# NOMIDI_Controller_005_fix.net
KiCad netlist of a schematic drawn in EAGLE
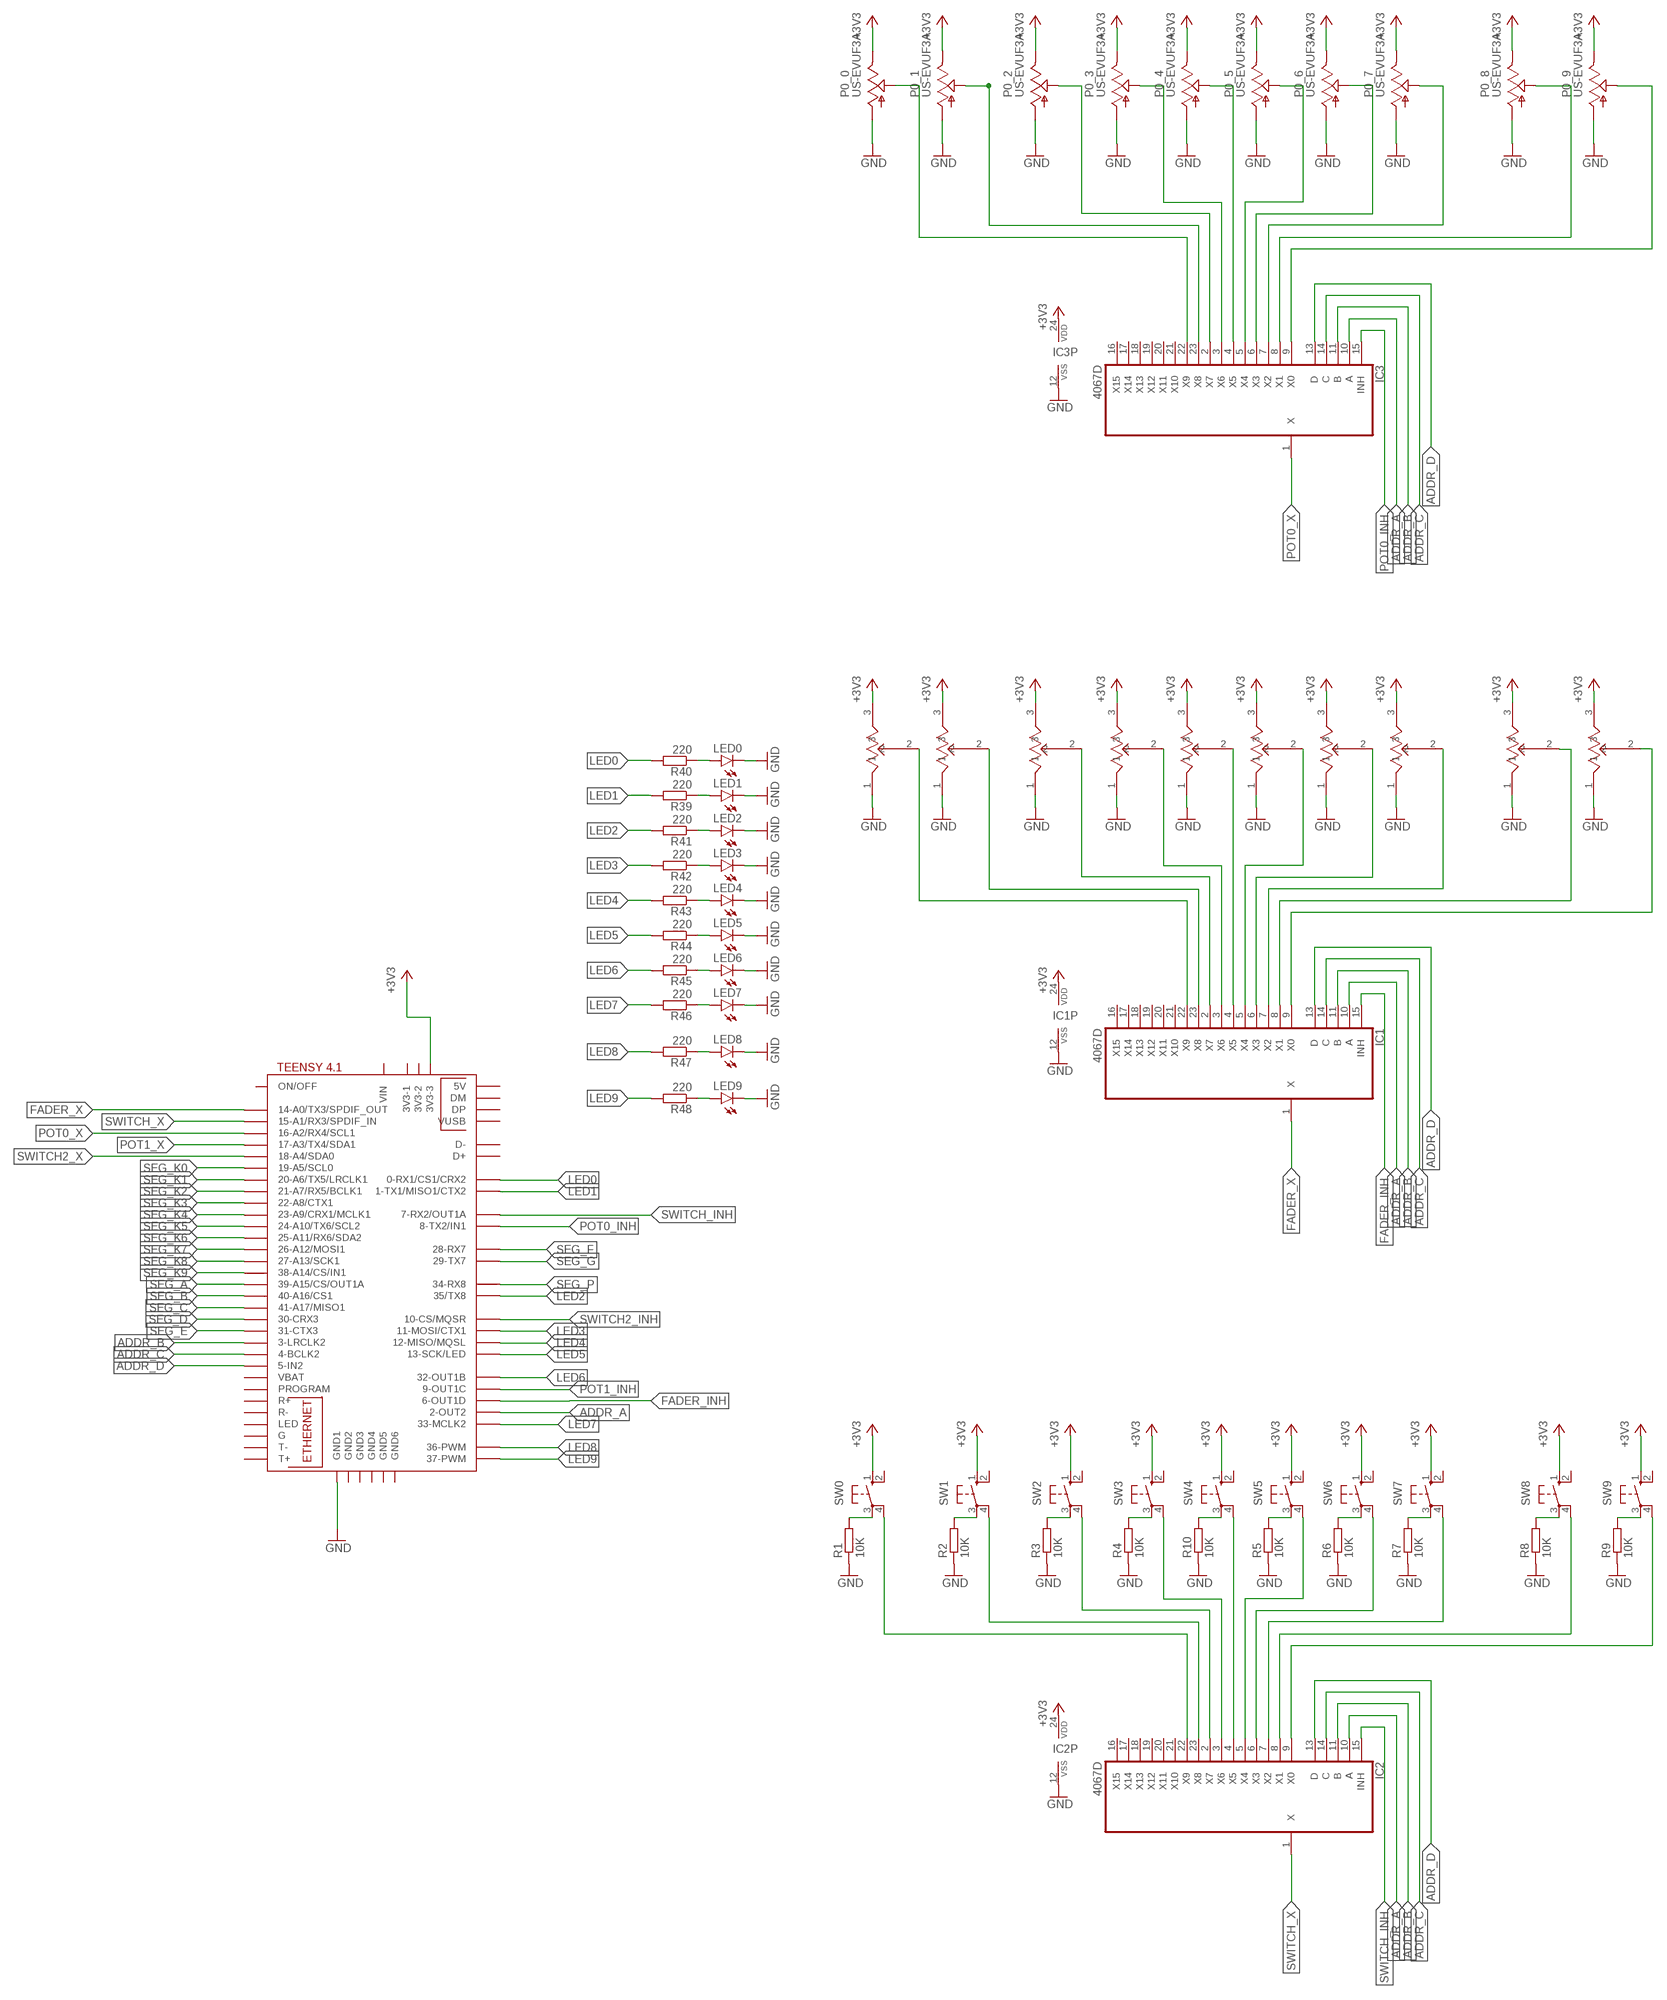
[diagram p0: schematic, sheet 1, part 1 of 3]
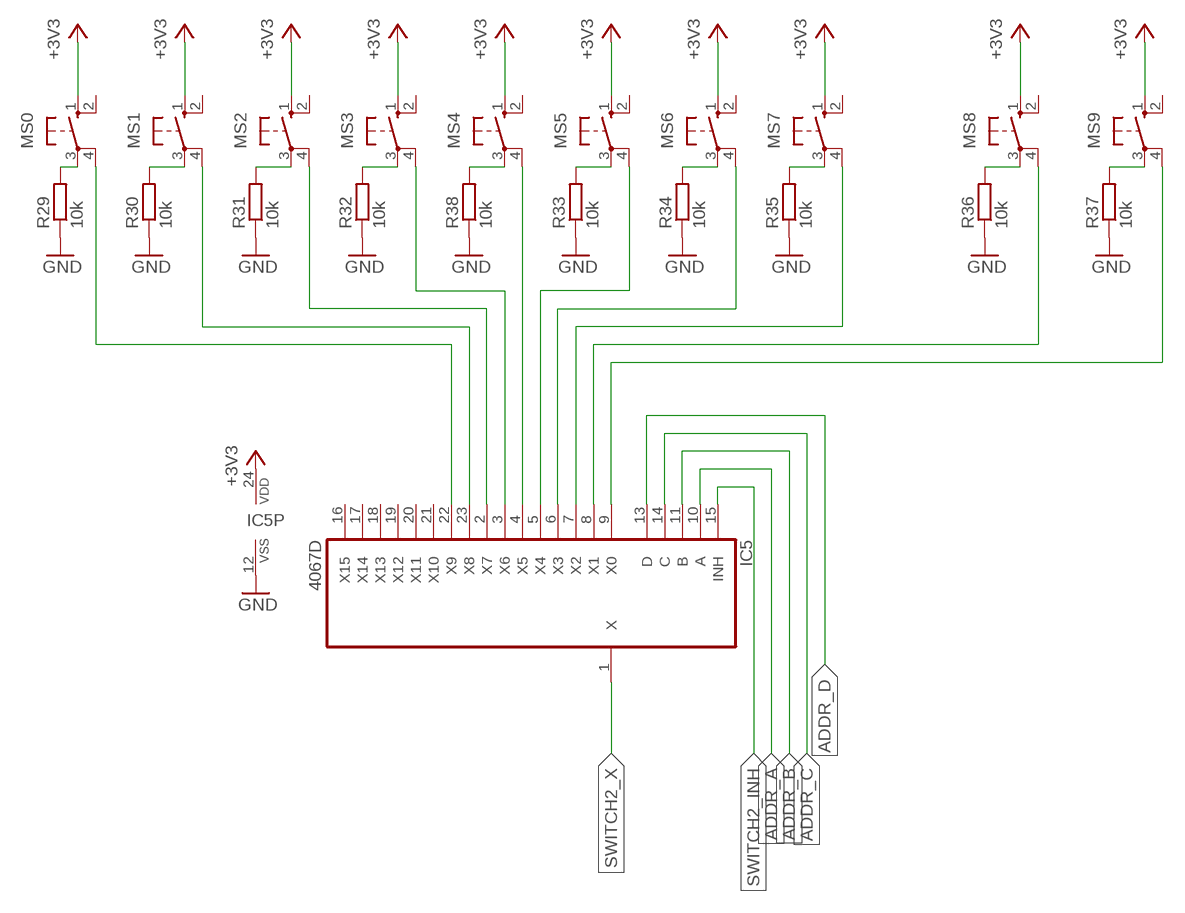
[diagram p1: schematic, sheet 1, part 2 of 3]
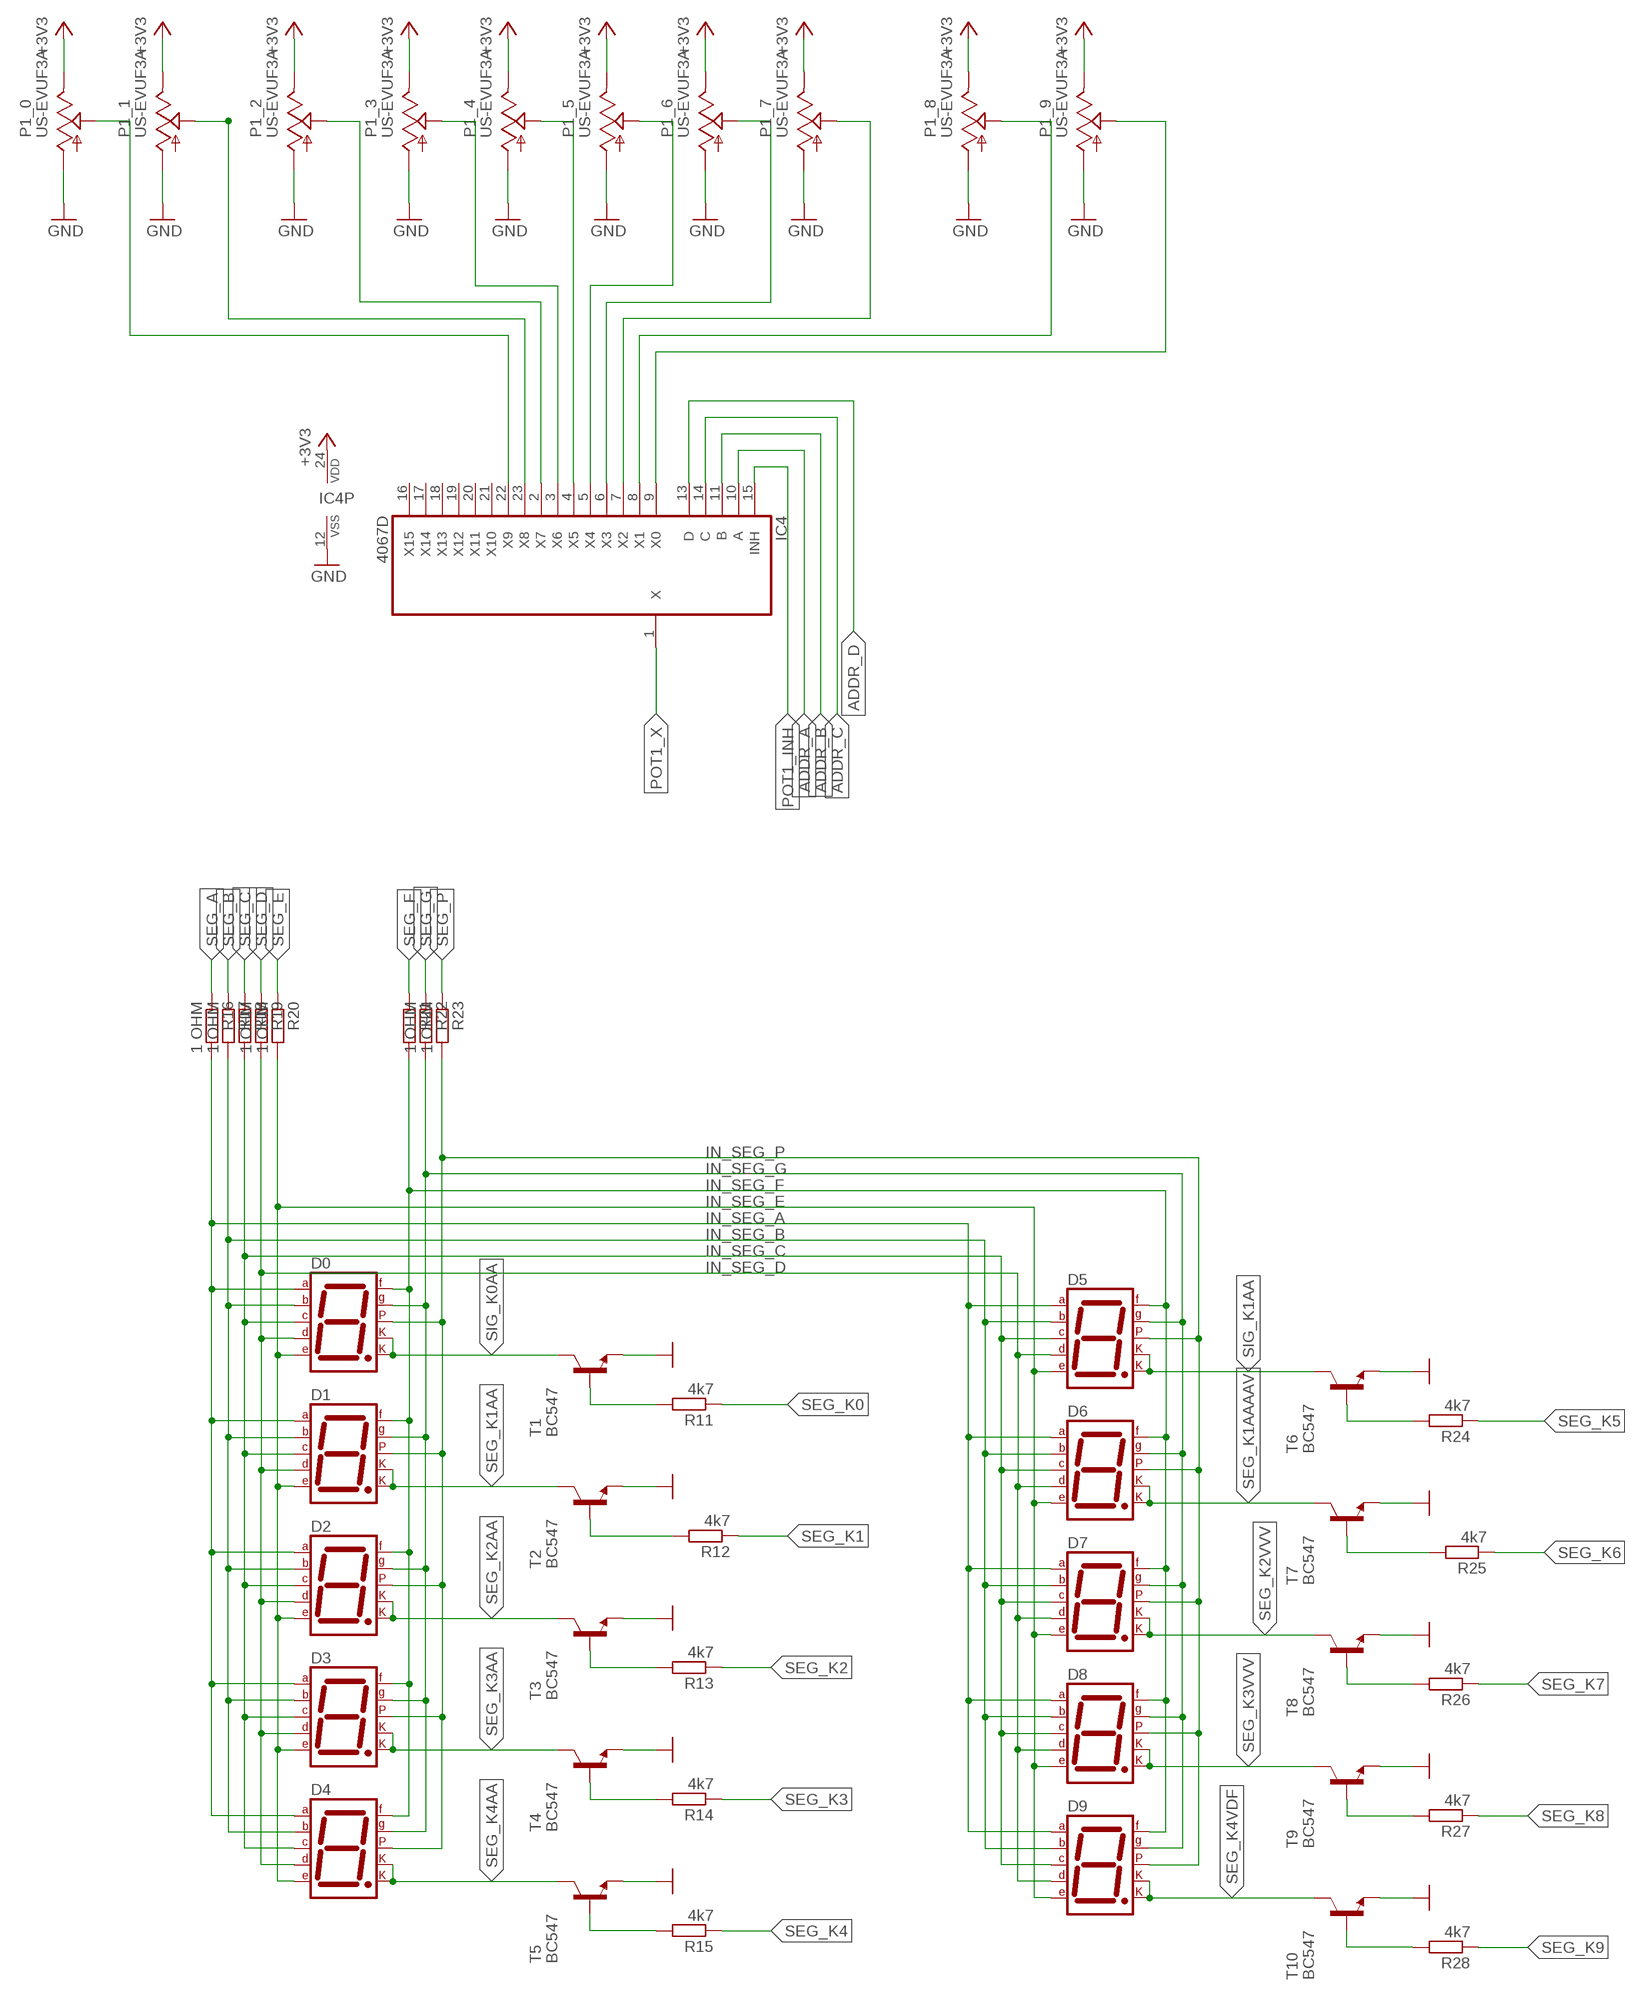
[diagram p2: schematic, sheet 1, part 3 of 3]

(export (version "E")
  (design (tool "Eeschema 10.0.6"))
  (components
    (comp (ref "D0")
      (value "7SEG-CK")
      (footprint "eagle-import:7SEG-13")
      (libsource (lib "eagle-import") (part "7SEG-CK"))
    )
    (comp (ref "D1")
      (value "7SEG-CK")
      (footprint "eagle-import:7SEG-13")
      (libsource (lib "eagle-import") (part "7SEG-CK"))
    )
    (comp (ref "D2")
      (value "7SEG-CK")
      (footprint "eagle-import:7SEG-13")
      (libsource (lib "eagle-import") (part "7SEG-CK"))
    )
    (comp (ref "D3")
      (value "7SEG-CK")
      (footprint "eagle-import:7SEG-13")
      (libsource (lib "eagle-import") (part "7SEG-CK"))
    )
    (comp (ref "D4")
      (value "7SEG-CK")
      (footprint "eagle-import:7SEG-13")
      (libsource (lib "eagle-import") (part "7SEG-CK"))
    )
    (comp (ref "D5")
      (value "7SEG-CK")
      (footprint "eagle-import:7SEG-13")
      (libsource (lib "eagle-import") (part "7SEG-CK"))
    )
    (comp (ref "D6")
      (value "7SEG-CK")
      (footprint "eagle-import:7SEG-13")
      (libsource (lib "eagle-import") (part "7SEG-CK"))
    )
    (comp (ref "D7")
      (value "7SEG-CK")
      (footprint "eagle-import:7SEG-13")
      (libsource (lib "eagle-import") (part "7SEG-CK"))
    )
    (comp (ref "D8")
      (value "7SEG-CK")
      (footprint "eagle-import:7SEG-13")
      (libsource (lib "eagle-import") (part "7SEG-CK"))
    )
    (comp (ref "D9")
      (value "7SEG-CK")
      (footprint "eagle-import:7SEG-13")
      (libsource (lib "eagle-import") (part "7SEG-CK"))
    )
    (comp (ref "IC1")
      (value "4067D")
      (footprint "eagle-import:SO24W")
      (libsource (lib "eagle-import") (part "4067D"))
    )
    (comp (ref "IC2")
      (value "4067D")
      (footprint "eagle-import:SO24W")
      (libsource (lib "eagle-import") (part "4067D"))
    )
    (comp (ref "IC3")
      (value "4067D")
      (footprint "eagle-import:SO24W")
      (libsource (lib "eagle-import") (part "4067D"))
    )
    (comp (ref "IC4")
      (value "4067D")
      (footprint "eagle-import:SO24W")
      (libsource (lib "eagle-import") (part "4067D"))
    )
    (comp (ref "IC5")
      (value "4067D")
      (footprint "eagle-import:SO24W")
      (libsource (lib "eagle-import") (part "4067D"))
    )
    (comp (ref "LED0")
      (value "LED3MM")
      (footprint "eagle-import:LED3MM")
      (libsource (lib "eagle-import") (part "LED3MM"))
    )
    (comp (ref "LED1")
      (value "LED3MM")
      (footprint "eagle-import:LED3MM")
      (libsource (lib "eagle-import") (part "LED3MM"))
    )
    (comp (ref "LED2")
      (value "LED3MM")
      (footprint "eagle-import:LED3MM")
      (libsource (lib "eagle-import") (part "LED3MM"))
    )
    (comp (ref "LED3")
      (value "LED3MM")
      (footprint "eagle-import:LED3MM")
      (libsource (lib "eagle-import") (part "LED3MM"))
    )
    (comp (ref "LED4")
      (value "LED3MM")
      (footprint "eagle-import:LED3MM")
      (libsource (lib "eagle-import") (part "LED3MM"))
    )
    (comp (ref "LED5")
      (value "LED3MM")
      (footprint "eagle-import:LED3MM")
      (libsource (lib "eagle-import") (part "LED3MM"))
    )
    (comp (ref "LED6")
      (value "LED3MM")
      (footprint "eagle-import:LED3MM")
      (libsource (lib "eagle-import") (part "LED3MM"))
    )
    (comp (ref "LED7")
      (value "LED3MM")
      (footprint "eagle-import:LED3MM")
      (libsource (lib "eagle-import") (part "LED3MM"))
    )
    (comp (ref "LED8")
      (value "LED3MM")
      (footprint "eagle-import:LED3MM")
      (libsource (lib "eagle-import") (part "LED3MM"))
    )
    (comp (ref "LED9")
      (value "LED3MM")
      (footprint "eagle-import:LED3MM")
      (libsource (lib "eagle-import") (part "LED3MM"))
    )
    (comp (ref "M0")
      (value "SLIDEPOT-ALPS-60MM")
      (footprint "eagle-import:RS6011SP600")
      (libsource (lib "eagle-import") (part "SLIDEPOT-ALPS-60MM"))
    )
    (comp (ref "M1")
      (value "SLIDEPOT-ALPS-60MM")
      (footprint "eagle-import:RS6011SP600")
      (libsource (lib "eagle-import") (part "SLIDEPOT-ALPS-60MM"))
    )
    (comp (ref "MS0")
      (value "10-XX")
      (footprint "eagle-import:B3F-10XX")
      (fields (field (name "MPN") "B3F-1000"))
      (libsource (lib "eagle-import") (part "10-XX"))
    )
    (comp (ref "MS1")
      (value "10-XX")
      (footprint "eagle-import:B3F-10XX")
      (fields (field (name "MPN") "B3F-1000"))
      (libsource (lib "eagle-import") (part "10-XX"))
    )
    (comp (ref "MS2")
      (value "10-XX")
      (footprint "eagle-import:B3F-10XX")
      (fields (field (name "MPN") "B3F-1000"))
      (libsource (lib "eagle-import") (part "10-XX"))
    )
    (comp (ref "MS3")
      (value "10-XX")
      (footprint "eagle-import:B3F-10XX")
      (fields (field (name "MPN") "B3F-1000"))
      (libsource (lib "eagle-import") (part "10-XX"))
    )
    (comp (ref "MS4")
      (value "10-XX")
      (footprint "eagle-import:B3F-10XX")
      (fields (field (name "MPN") "B3F-1000"))
      (libsource (lib "eagle-import") (part "10-XX"))
    )
    (comp (ref "MS5")
      (value "10-XX")
      (footprint "eagle-import:B3F-10XX")
      (fields (field (name "MPN") "B3F-1000"))
      (libsource (lib "eagle-import") (part "10-XX"))
    )
    (comp (ref "MS6")
      (value "10-XX")
      (footprint "eagle-import:B3F-10XX")
      (fields (field (name "MPN") "B3F-1000"))
      (libsource (lib "eagle-import") (part "10-XX"))
    )
    (comp (ref "MS7")
      (value "10-XX")
      (footprint "eagle-import:B3F-10XX")
      (fields (field (name "MPN") "B3F-1000"))
      (libsource (lib "eagle-import") (part "10-XX"))
    )
    (comp (ref "MS8")
      (value "10-XX")
      (footprint "eagle-import:B3F-10XX")
      (fields (field (name "MPN") "B3F-1000"))
      (libsource (lib "eagle-import") (part "10-XX"))
    )
    (comp (ref "MS9")
      (value "10-XX")
      (footprint "eagle-import:B3F-10XX")
      (fields (field (name "MPN") "B3F-1000"))
      (libsource (lib "eagle-import") (part "10-XX"))
    )
    (comp (ref "P0_0")
      (value "US-EVUF3A")
      (footprint "eagle-import:EVUF")
      (libsource (lib "eagle-import") (part "US-EVUAF3"))
    )
    (comp (ref "P0_1")
      (value "US-EVUF3A")
      (footprint "eagle-import:EVUF")
      (libsource (lib "eagle-import") (part "US-EVUAF3"))
    )
    (comp (ref "P0_2")
      (value "US-EVUF3A")
      (footprint "eagle-import:EVUF")
      (libsource (lib "eagle-import") (part "US-EVUAF3"))
    )
    (comp (ref "P0_3")
      (value "US-EVUF3A")
      (footprint "eagle-import:EVUF")
      (libsource (lib "eagle-import") (part "US-EVUAF3"))
    )
    (comp (ref "P0_4")
      (value "US-EVUF3A")
      (footprint "eagle-import:EVUF")
      (libsource (lib "eagle-import") (part "US-EVUAF3"))
    )
    (comp (ref "P0_5")
      (value "US-EVUF3A")
      (footprint "eagle-import:EVUF")
      (libsource (lib "eagle-import") (part "US-EVUAF3"))
    )
    (comp (ref "P0_6")
      (value "US-EVUF3A")
      (footprint "eagle-import:EVUF")
      (libsource (lib "eagle-import") (part "US-EVUAF3"))
    )
    (comp (ref "P0_7")
      (value "US-EVUF3A")
      (footprint "eagle-import:EVUF")
      (libsource (lib "eagle-import") (part "US-EVUAF3"))
    )
    (comp (ref "P0_8")
      (value "US-EVUF3A")
      (footprint "eagle-import:EVUF")
      (libsource (lib "eagle-import") (part "US-EVUAF3"))
    )
    (comp (ref "P0_9")
      (value "US-EVUF3A")
      (footprint "eagle-import:EVUF")
      (libsource (lib "eagle-import") (part "US-EVUAF3"))
    )
    (comp (ref "P1_0")
      (value "US-EVUF3A")
      (footprint "eagle-import:EVUF")
      (libsource (lib "eagle-import") (part "US-EVUAF3"))
    )
    (comp (ref "P1_1")
      (value "US-EVUF3A")
      (footprint "eagle-import:EVUF")
      (libsource (lib "eagle-import") (part "US-EVUAF3"))
    )
    (comp (ref "P1_2")
      (value "US-EVUF3A")
      (footprint "eagle-import:EVUF")
      (libsource (lib "eagle-import") (part "US-EVUAF3"))
    )
    (comp (ref "P1_3")
      (value "US-EVUF3A")
      (footprint "eagle-import:EVUF")
      (libsource (lib "eagle-import") (part "US-EVUAF3"))
    )
    (comp (ref "P1_4")
      (value "US-EVUF3A")
      (footprint "eagle-import:EVUF")
      (libsource (lib "eagle-import") (part "US-EVUAF3"))
    )
    (comp (ref "P1_5")
      (value "US-EVUF3A")
      (footprint "eagle-import:EVUF")
      (libsource (lib "eagle-import") (part "US-EVUAF3"))
    )
    (comp (ref "P1_6")
      (value "US-EVUF3A")
      (footprint "eagle-import:EVUF")
      (libsource (lib "eagle-import") (part "US-EVUAF3"))
    )
    (comp (ref "P1_7")
      (value "US-EVUF3A")
      (footprint "eagle-import:EVUF")
      (libsource (lib "eagle-import") (part "US-EVUAF3"))
    )
    (comp (ref "P1_8")
      (value "US-EVUF3A")
      (footprint "eagle-import:EVUF")
      (libsource (lib "eagle-import") (part "US-EVUAF3"))
    )
    (comp (ref "P1_9")
      (value "US-EVUF3A")
      (footprint "eagle-import:EVUF")
      (libsource (lib "eagle-import") (part "US-EVUAF3"))
    )
    (comp (ref "R1")
      (value "10K")
      (footprint "eagle-import:0207_7")
      (libsource (lib "eagle-import") (part "R-EU_0207/7"))
    )
    (comp (ref "R2")
      (value "10K")
      (footprint "eagle-import:0207_7")
      (libsource (lib "eagle-import") (part "R-EU_0207/7"))
    )
    (comp (ref "R3")
      (value "10K")
      (footprint "eagle-import:0207_7")
      (libsource (lib "eagle-import") (part "R-EU_0207/7"))
    )
    (comp (ref "R4")
      (value "10K")
      (footprint "eagle-import:0207_7")
      (libsource (lib "eagle-import") (part "R-EU_0207/7"))
    )
    (comp (ref "R5")
      (value "10K")
      (footprint "eagle-import:0207_7")
      (libsource (lib "eagle-import") (part "R-EU_0207/7"))
    )
    (comp (ref "R6")
      (value "10K")
      (footprint "eagle-import:0207_7")
      (libsource (lib "eagle-import") (part "R-EU_0207/7"))
    )
    (comp (ref "R7")
      (value "10K")
      (footprint "eagle-import:0207_7")
      (libsource (lib "eagle-import") (part "R-EU_0207/7"))
    )
    (comp (ref "R8")
      (value "10K")
      (footprint "eagle-import:0207_7")
      (libsource (lib "eagle-import") (part "R-EU_0207/7"))
    )
    (comp (ref "R9")
      (value "10K")
      (footprint "eagle-import:0207_7")
      (libsource (lib "eagle-import") (part "R-EU_0207/7"))
    )
    (comp (ref "R10")
      (value "10K")
      (footprint "eagle-import:0207_7")
      (libsource (lib "eagle-import") (part "R-EU_0207/7"))
    )
    (comp (ref "R11")
      (value "4k7")
      (footprint "eagle-import:0207_7")
      (libsource (lib "eagle-import") (part "R-EU_0207/7"))
    )
    (comp (ref "R12")
      (value "4k7")
      (footprint "eagle-import:0207_7")
      (libsource (lib "eagle-import") (part "R-EU_0207/7"))
    )
    (comp (ref "R13")
      (value "4k7")
      (footprint "eagle-import:0207_7")
      (libsource (lib "eagle-import") (part "R-EU_0207/7"))
    )
    (comp (ref "R14")
      (value "4k7")
      (footprint "eagle-import:0207_7")
      (libsource (lib "eagle-import") (part "R-EU_0207/7"))
    )
    (comp (ref "R15")
      (value "4k7")
      (footprint "eagle-import:0207_7")
      (libsource (lib "eagle-import") (part "R-EU_0207/7"))
    )
    (comp (ref "R16")
      (value "1 OHM")
      (footprint "eagle-import:0207_7")
      (libsource (lib "eagle-import") (part "R-EU_0207/7"))
    )
    (comp (ref "R17")
      (value "1 OHM")
      (footprint "eagle-import:0207_7")
      (libsource (lib "eagle-import") (part "R-EU_0207/7"))
    )
    (comp (ref "R18")
      (value "R-EU_0207/7")
      (footprint "eagle-import:0207_7")
      (libsource (lib "eagle-import") (part "R-EU_0207/7"))
    )
    (comp (ref "R19")
      (value "1 OHM")
      (footprint "eagle-import:0207_7")
      (libsource (lib "eagle-import") (part "R-EU_0207/7"))
    )
    (comp (ref "R20")
      (value "1 OHM")
      (footprint "eagle-import:0207_7")
      (libsource (lib "eagle-import") (part "R-EU_0207/7"))
    )
    (comp (ref "R21")
      (value "R-EU_0207/7")
      (footprint "eagle-import:0207_7")
      (libsource (lib "eagle-import") (part "R-EU_0207/7"))
    )
    (comp (ref "R22")
      (value "1 OHM")
      (footprint "eagle-import:0207_7")
      (libsource (lib "eagle-import") (part "R-EU_0207/7"))
    )
    (comp (ref "R23")
      (value "1 OHM")
      (footprint "eagle-import:0207_7")
      (libsource (lib "eagle-import") (part "R-EU_0207/7"))
    )
    (comp (ref "R24")
      (value "4k7")
      (footprint "eagle-import:0207_7")
      (libsource (lib "eagle-import") (part "R-EU_0207/7"))
    )
    (comp (ref "R25")
      (value "4k7")
      (footprint "eagle-import:0207_7")
      (libsource (lib "eagle-import") (part "R-EU_0207/7"))
    )
    (comp (ref "R26")
      (value "4k7")
      (footprint "eagle-import:0207_7")
      (libsource (lib "eagle-import") (part "R-EU_0207/7"))
    )
    (comp (ref "R27")
      (value "4k7")
      (footprint "eagle-import:0207_7")
      (libsource (lib "eagle-import") (part "R-EU_0207/7"))
    )
    (comp (ref "R28")
      (value "4k7")
      (footprint "eagle-import:0207_7")
      (libsource (lib "eagle-import") (part "R-EU_0207/7"))
    )
    (comp (ref "R29")
      (value "10k")
      (footprint "eagle-import:0207_7")
      (libsource (lib "eagle-import") (part "R-EU_0207/7"))
    )
    (comp (ref "R30")
      (value "10k")
      (footprint "eagle-import:0207_7")
      (libsource (lib "eagle-import") (part "R-EU_0207/7"))
    )
    (comp (ref "R31")
      (value "10k")
      (footprint "eagle-import:0207_7")
      (libsource (lib "eagle-import") (part "R-EU_0207/7"))
    )
    (comp (ref "R32")
      (value "10k")
      (footprint "eagle-import:0207_7")
      (libsource (lib "eagle-import") (part "R-EU_0207/7"))
    )
    (comp (ref "R33")
      (value "10k")
      (footprint "eagle-import:0207_7")
      (libsource (lib "eagle-import") (part "R-EU_0207/7"))
    )
    (comp (ref "R34")
      (value "10k")
      (footprint "eagle-import:0207_7")
      (libsource (lib "eagle-import") (part "R-EU_0207/7"))
    )
    (comp (ref "R35")
      (value "10k")
      (footprint "eagle-import:0207_7")
      (libsource (lib "eagle-import") (part "R-EU_0207/7"))
    )
    (comp (ref "R36")
      (value "10k")
      (footprint "eagle-import:0207_7")
      (libsource (lib "eagle-import") (part "R-EU_0207/7"))
    )
    (comp (ref "R37")
      (value "10k")
      (footprint "eagle-import:0207_7")
      (libsource (lib "eagle-import") (part "R-EU_0207/7"))
    )
    (comp (ref "R38")
      (value "10k")
      (footprint "eagle-import:0207_7")
      (libsource (lib "eagle-import") (part "R-EU_0207/7"))
    )
    (comp (ref "R39")
      (value "220")
      (footprint "eagle-import:0207_7")
      (libsource (lib "eagle-import") (part "R-EU_0207/7"))
    )
    (comp (ref "R40")
      (value "220")
      (footprint "eagle-import:0207_7")
      (libsource (lib "eagle-import") (part "R-EU_0207/7"))
    )
    (comp (ref "R41")
      (value "220")
      (footprint "eagle-import:0207_7")
      (libsource (lib "eagle-import") (part "R-EU_0207/7"))
    )
    (comp (ref "R42")
      (value "220")
      (footprint "eagle-import:0207_7")
      (libsource (lib "eagle-import") (part "R-EU_0207/7"))
    )
    (comp (ref "R43")
      (value "220")
      (footprint "eagle-import:0207_7")
      (libsource (lib "eagle-import") (part "R-EU_0207/7"))
    )
    (comp (ref "R44")
      (value "220")
      (footprint "eagle-import:0207_7")
      (libsource (lib "eagle-import") (part "R-EU_0207/7"))
    )
    (comp (ref "R45")
      (value "220")
      (footprint "eagle-import:0207_7")
      (libsource (lib "eagle-import") (part "R-EU_0207/7"))
    )
    (comp (ref "R46")
      (value "220")
      (footprint "eagle-import:0207_7")
      (libsource (lib "eagle-import") (part "R-EU_0207/7"))
    )
    (comp (ref "R47")
      (value "220")
      (footprint "eagle-import:0207_7")
      (libsource (lib "eagle-import") (part "R-EU_0207/7"))
    )
    (comp (ref "R48")
      (value "220")
      (footprint "eagle-import:0207_7")
      (libsource (lib "eagle-import") (part "R-EU_0207/7"))
    )
    (comp (ref "S0")
      (value "SLIDEPOT-ALPS-60MM")
      (footprint "eagle-import:RS6011SP600")
      (libsource (lib "eagle-import") (part "SLIDEPOT-ALPS-60MM"))
    )
    (comp (ref "S1")
      (value "SLIDEPOT-ALPS-60MM")
      (footprint "eagle-import:RS6011SP600")
      (libsource (lib "eagle-import") (part "SLIDEPOT-ALPS-60MM"))
    )
    (comp (ref "S2")
      (value "SLIDEPOT-ALPS-60MM")
      (footprint "eagle-import:RS6011SP600")
      (libsource (lib "eagle-import") (part "SLIDEPOT-ALPS-60MM"))
    )
    (comp (ref "S3")
      (value "SLIDEPOT-ALPS-60MM")
      (footprint "eagle-import:RS6011SP600")
      (libsource (lib "eagle-import") (part "SLIDEPOT-ALPS-60MM"))
    )
    (comp (ref "S4")
      (value "SLIDEPOT-ALPS-60MM")
      (footprint "eagle-import:RS6011SP600")
      (libsource (lib "eagle-import") (part "SLIDEPOT-ALPS-60MM"))
    )
    (comp (ref "S5")
      (value "SLIDEPOT-ALPS-60MM")
      (footprint "eagle-import:RS6011SP600")
      (libsource (lib "eagle-import") (part "SLIDEPOT-ALPS-60MM"))
    )
    (comp (ref "S6")
      (value "SLIDEPOT-ALPS-60MM")
      (footprint "eagle-import:RS6011SP600")
      (libsource (lib "eagle-import") (part "SLIDEPOT-ALPS-60MM"))
    )
    (comp (ref "S7")
      (value "SLIDEPOT-ALPS-60MM")
      (footprint "eagle-import:RS6011SP600")
      (libsource (lib "eagle-import") (part "SLIDEPOT-ALPS-60MM"))
    )
    (comp (ref "SW0")
      (value "10-XX")
      (footprint "eagle-import:B3F-10XX")
      (fields (field (name "MPN") "B3F-1000"))
      (libsource (lib "eagle-import") (part "10-XX"))
    )
    (comp (ref "SW1")
      (value "10-XX")
      (footprint "eagle-import:B3F-10XX")
      (fields (field (name "MPN") "B3F-1000"))
      (libsource (lib "eagle-import") (part "10-XX"))
    )
    (comp (ref "SW2")
      (value "10-XX")
      (footprint "eagle-import:B3F-10XX")
      (fields (field (name "MPN") "B3F-1000"))
      (libsource (lib "eagle-import") (part "10-XX"))
    )
    (comp (ref "SW3")
      (value "10-XX")
      (footprint "eagle-import:B3F-10XX")
      (fields (field (name "MPN") "B3F-1000"))
      (libsource (lib "eagle-import") (part "10-XX"))
    )
    (comp (ref "SW4")
      (value "10-XX")
      (footprint "eagle-import:B3F-10XX")
      (fields (field (name "MPN") "B3F-1000"))
      (libsource (lib "eagle-import") (part "10-XX"))
    )
    (comp (ref "SW5")
      (value "10-XX")
      (footprint "eagle-import:B3F-10XX")
      (fields (field (name "MPN") "B3F-1000"))
      (libsource (lib "eagle-import") (part "10-XX"))
    )
    (comp (ref "SW6")
      (value "10-XX")
      (footprint "eagle-import:B3F-10XX")
      (fields (field (name "MPN") "B3F-1000"))
      (libsource (lib "eagle-import") (part "10-XX"))
    )
    (comp (ref "SW7")
      (value "10-XX")
      (footprint "eagle-import:B3F-10XX")
      (fields (field (name "MPN") "B3F-1000"))
      (libsource (lib "eagle-import") (part "10-XX"))
    )
    (comp (ref "SW8")
      (value "10-XX")
      (footprint "eagle-import:B3F-10XX")
      (fields (field (name "MPN") "B3F-1000"))
      (libsource (lib "eagle-import") (part "10-XX"))
    )
    (comp (ref "SW9")
      (value "10-XX")
      (footprint "eagle-import:B3F-10XX")
      (fields (field (name "MPN") "B3F-1000"))
      (libsource (lib "eagle-import") (part "10-XX"))
    )
    (comp (ref "T1")
      (value "BC547")
      (footprint "eagle-import:TO92")
      (libsource (lib "eagle-import") (part "BC547"))
    )
    (comp (ref "T2")
      (value "BC547")
      (footprint "eagle-import:TO92")
      (libsource (lib "eagle-import") (part "BC547"))
    )
    (comp (ref "T3")
      (value "BC547")
      (footprint "eagle-import:TO92")
      (libsource (lib "eagle-import") (part "BC547"))
    )
    (comp (ref "T4")
      (value "BC547")
      (footprint "eagle-import:TO92")
      (libsource (lib "eagle-import") (part "BC547"))
    )
    (comp (ref "T5")
      (value "BC547")
      (footprint "eagle-import:TO92")
      (libsource (lib "eagle-import") (part "BC547"))
    )
    (comp (ref "T6")
      (value "BC547")
      (footprint "eagle-import:TO92")
      (libsource (lib "eagle-import") (part "BC547"))
    )
    (comp (ref "T7")
      (value "BC547")
      (footprint "eagle-import:TO92")
      (libsource (lib "eagle-import") (part "BC547"))
    )
    (comp (ref "T8")
      (value "BC547")
      (footprint "eagle-import:TO92")
      (libsource (lib "eagle-import") (part "BC547"))
    )
    (comp (ref "T9")
      (value "BC547")
      (footprint "eagle-import:TO92")
      (libsource (lib "eagle-import") (part "BC547"))
    )
    (comp (ref "T10")
      (value "BC547")
      (footprint "eagle-import:TO92")
      (libsource (lib "eagle-import") (part "BC547"))
    )
    (comp (ref "U$1")
      (value "TEENSY41")
      (footprint "eagle-import:TEENSY41")
      (libsource (lib "eagle-import") (part "TEENSY41"))
    )
  )
  (nets
    (net (code "1") (name "+3V3") (class "Default")
      (node (ref "IC1") (pin "24") (pinfunction "VDD_24") (pintype "power_in"))
      (node (ref "IC2") (pin "24") (pinfunction "VDD_24") (pintype "power_in"))
      (node (ref "IC3") (pin "24") (pinfunction "VDD_24") (pintype "power_in"))
      (node (ref "IC4") (pin "24") (pinfunction "VDD_24") (pintype "power_in"))
      (node (ref "IC5") (pin "24") (pinfunction "VDD_24") (pintype "power_in"))
      (node (ref "M0") (pin "3") (pinfunction "3_3") (pintype "bidirectional"))
      (node (ref "M1") (pin "3") (pinfunction "3_3") (pintype "bidirectional"))
      (node (ref "MS0") (pin "1") (pinfunction "S_1") (pintype "passive"))
      (node (ref "MS1") (pin "1") (pinfunction "S_1") (pintype "passive"))
      (node (ref "MS2") (pin "1") (pinfunction "S_1") (pintype "passive"))
      (node (ref "MS3") (pin "1") (pinfunction "S_1") (pintype "passive"))
      (node (ref "MS4") (pin "1") (pinfunction "S_1") (pintype "passive"))
      (node (ref "MS5") (pin "1") (pinfunction "S_1") (pintype "passive"))
      (node (ref "MS6") (pin "1") (pinfunction "S_1") (pintype "passive"))
      (node (ref "MS7") (pin "1") (pinfunction "S_1") (pintype "passive"))
      (node (ref "MS8") (pin "1") (pinfunction "S_1") (pintype "passive"))
      (node (ref "MS9") (pin "1") (pinfunction "S_1") (pintype "passive"))
      (node (ref "P0_0") (pin "3") (pinfunction "E_3") (pintype "passive"))
      (node (ref "P0_1") (pin "3") (pinfunction "E_3") (pintype "passive"))
      (node (ref "P0_2") (pin "3") (pinfunction "E_3") (pintype "passive"))
      (node (ref "P0_3") (pin "3") (pinfunction "E_3") (pintype "passive"))
      (node (ref "P0_4") (pin "3") (pinfunction "E_3") (pintype "passive"))
      (node (ref "P0_5") (pin "3") (pinfunction "E_3") (pintype "passive"))
      (node (ref "P0_6") (pin "3") (pinfunction "E_3") (pintype "passive"))
      (node (ref "P0_7") (pin "3") (pinfunction "E_3") (pintype "passive"))
      (node (ref "P0_8") (pin "3") (pinfunction "E_3") (pintype "passive"))
      (node (ref "P0_9") (pin "3") (pinfunction "E_3") (pintype "passive"))
      (node (ref "P1_0") (pin "3") (pinfunction "E_3") (pintype "passive"))
      (node (ref "P1_1") (pin "3") (pinfunction "E_3") (pintype "passive"))
      (node (ref "P1_2") (pin "3") (pinfunction "E_3") (pintype "passive"))
      (node (ref "P1_3") (pin "3") (pinfunction "E_3") (pintype "passive"))
      (node (ref "P1_4") (pin "3") (pinfunction "E_3") (pintype "passive"))
      (node (ref "P1_5") (pin "3") (pinfunction "E_3") (pintype "passive"))
      (node (ref "P1_6") (pin "3") (pinfunction "E_3") (pintype "passive"))
      (node (ref "P1_7") (pin "3") (pinfunction "E_3") (pintype "passive"))
      (node (ref "P1_8") (pin "3") (pinfunction "E_3") (pintype "passive"))
      (node (ref "P1_9") (pin "3") (pinfunction "E_3") (pintype "passive"))
      (node (ref "S0") (pin "3") (pinfunction "3_3") (pintype "bidirectional"))
      (node (ref "S1") (pin "3") (pinfunction "3_3") (pintype "bidirectional"))
      (node (ref "S2") (pin "3") (pinfunction "3_3") (pintype "bidirectional"))
      (node (ref "S3") (pin "3") (pinfunction "3_3") (pintype "bidirectional"))
      (node (ref "S4") (pin "3") (pinfunction "3_3") (pintype "bidirectional"))
      (node (ref "S5") (pin "3") (pinfunction "3_3") (pintype "bidirectional"))
      (node (ref "S6") (pin "3") (pinfunction "3_3") (pintype "bidirectional"))
      (node (ref "S7") (pin "3") (pinfunction "3_3") (pintype "bidirectional"))
      (node (ref "SW0") (pin "1") (pinfunction "S_1") (pintype "passive"))
      (node (ref "SW1") (pin "1") (pinfunction "S_1") (pintype "passive"))
      (node (ref "SW2") (pin "1") (pinfunction "S_1") (pintype "passive"))
      (node (ref "SW3") (pin "1") (pinfunction "S_1") (pintype "passive"))
      (node (ref "SW4") (pin "1") (pinfunction "S_1") (pintype "passive"))
      (node (ref "SW5") (pin "1") (pinfunction "S_1") (pintype "passive"))
      (node (ref "SW6") (pin "1") (pinfunction "S_1") (pintype "passive"))
      (node (ref "SW7") (pin "1") (pinfunction "S_1") (pintype "passive"))
      (node (ref "SW8") (pin "1") (pinfunction "S_1") (pintype "passive"))
      (node (ref "SW9") (pin "1") (pinfunction "S_1") (pintype "passive"))
      (node (ref "U$1") (pin "3V3-3") (pinfunction "3V3-3_3V3-3") (pintype "bidirectional"))
    )
    (net (code "2") (name "/IN_SEG_A") (class "Default")
      (node (ref "D0") (pin "7") (pinfunction "A_7") (pintype "passive"))
      (node (ref "D1") (pin "7") (pinfunction "A_7") (pintype "passive"))
      (node (ref "D2") (pin "7") (pinfunction "A_7") (pintype "passive"))
      (node (ref "D3") (pin "7") (pinfunction "A_7") (pintype "passive"))
      (node (ref "D4") (pin "7") (pinfunction "A_7") (pintype "passive"))
      (node (ref "D5") (pin "7") (pinfunction "A_7") (pintype "passive"))
      (node (ref "D6") (pin "7") (pinfunction "A_7") (pintype "passive"))
      (node (ref "D7") (pin "7") (pinfunction "A_7") (pintype "passive"))
      (node (ref "D8") (pin "7") (pinfunction "A_7") (pintype "passive"))
      (node (ref "D9") (pin "7") (pinfunction "A_7") (pintype "passive"))
      (node (ref "R16") (pin "2") (pinfunction "2_2") (pintype "passive"))
    )
    (net (code "3") (name "/IN_SEG_B") (class "Default")
      (node (ref "D0") (pin "6") (pinfunction "B_6") (pintype "passive"))
      (node (ref "D1") (pin "6") (pinfunction "B_6") (pintype "passive"))
      (node (ref "D2") (pin "6") (pinfunction "B_6") (pintype "passive"))
      (node (ref "D3") (pin "6") (pinfunction "B_6") (pintype "passive"))
      (node (ref "D4") (pin "6") (pinfunction "B_6") (pintype "passive"))
      (node (ref "D5") (pin "6") (pinfunction "B_6") (pintype "passive"))
      (node (ref "D6") (pin "6") (pinfunction "B_6") (pintype "passive"))
      (node (ref "D7") (pin "6") (pinfunction "B_6") (pintype "passive"))
      (node (ref "D8") (pin "6") (pinfunction "B_6") (pintype "passive"))
      (node (ref "D9") (pin "6") (pinfunction "B_6") (pintype "passive"))
      (node (ref "R17") (pin "2") (pinfunction "2_2") (pintype "passive"))
    )
    (net (code "4") (name "/IN_SEG_C") (class "Default")
      (node (ref "D0") (pin "4") (pinfunction "C_4") (pintype "passive"))
      (node (ref "D1") (pin "4") (pinfunction "C_4") (pintype "passive"))
      (node (ref "D2") (pin "4") (pinfunction "C_4") (pintype "passive"))
      (node (ref "D3") (pin "4") (pinfunction "C_4") (pintype "passive"))
      (node (ref "D4") (pin "4") (pinfunction "C_4") (pintype "passive"))
      (node (ref "D5") (pin "4") (pinfunction "C_4") (pintype "passive"))
      (node (ref "D6") (pin "4") (pinfunction "C_4") (pintype "passive"))
      (node (ref "D7") (pin "4") (pinfunction "C_4") (pintype "passive"))
      (node (ref "D8") (pin "4") (pinfunction "C_4") (pintype "passive"))
      (node (ref "D9") (pin "4") (pinfunction "C_4") (pintype "passive"))
      (node (ref "R18") (pin "2") (pinfunction "2_2") (pintype "passive"))
    )
    (net (code "5") (name "/IN_SEG_D") (class "Default")
      (node (ref "D0") (pin "2") (pinfunction "D_2") (pintype "passive"))
      (node (ref "D1") (pin "2") (pinfunction "D_2") (pintype "passive"))
      (node (ref "D2") (pin "2") (pinfunction "D_2") (pintype "passive"))
      (node (ref "D3") (pin "2") (pinfunction "D_2") (pintype "passive"))
      (node (ref "D4") (pin "2") (pinfunction "D_2") (pintype "passive"))
      (node (ref "D5") (pin "2") (pinfunction "D_2") (pintype "passive"))
      (node (ref "D6") (pin "2") (pinfunction "D_2") (pintype "passive"))
      (node (ref "D7") (pin "2") (pinfunction "D_2") (pintype "passive"))
      (node (ref "D8") (pin "2") (pinfunction "D_2") (pintype "passive"))
      (node (ref "D9") (pin "2") (pinfunction "D_2") (pintype "passive"))
      (node (ref "R19") (pin "2") (pinfunction "2_2") (pintype "passive"))
    )
    (net (code "6") (name "/IN_SEG_E") (class "Default")
      (node (ref "D0") (pin "1") (pinfunction "E_1") (pintype "passive"))
      (node (ref "D1") (pin "1") (pinfunction "E_1") (pintype "passive"))
      (node (ref "D2") (pin "1") (pinfunction "E_1") (pintype "passive"))
      (node (ref "D3") (pin "1") (pinfunction "E_1") (pintype "passive"))
      (node (ref "D4") (pin "1") (pinfunction "E_1") (pintype "passive"))
      (node (ref "D5") (pin "1") (pinfunction "E_1") (pintype "passive"))
      (node (ref "D6") (pin "1") (pinfunction "E_1") (pintype "passive"))
      (node (ref "D7") (pin "1") (pinfunction "E_1") (pintype "passive"))
      (node (ref "D8") (pin "1") (pinfunction "E_1") (pintype "passive"))
      (node (ref "D9") (pin "1") (pinfunction "E_1") (pintype "passive"))
      (node (ref "R20") (pin "2") (pinfunction "2_2") (pintype "passive"))
    )
    (net (code "7") (name "/IN_SEG_F") (class "Default")
      (node (ref "D0") (pin "9") (pinfunction "F_9") (pintype "passive"))
      (node (ref "D1") (pin "9") (pinfunction "F_9") (pintype "passive"))
      (node (ref "D2") (pin "9") (pinfunction "F_9") (pintype "passive"))
      (node (ref "D3") (pin "9") (pinfunction "F_9") (pintype "passive"))
      (node (ref "D4") (pin "9") (pinfunction "F_9") (pintype "passive"))
      (node (ref "D5") (pin "9") (pinfunction "F_9") (pintype "passive"))
      (node (ref "D6") (pin "9") (pinfunction "F_9") (pintype "passive"))
      (node (ref "D7") (pin "9") (pinfunction "F_9") (pintype "passive"))
      (node (ref "D8") (pin "9") (pinfunction "F_9") (pintype "passive"))
      (node (ref "D9") (pin "9") (pinfunction "F_9") (pintype "passive"))
      (node (ref "R21") (pin "2") (pinfunction "2_2") (pintype "passive"))
    )
    (net (code "8") (name "/IN_SEG_G") (class "Default")
      (node (ref "D0") (pin "10") (pinfunction "G_10") (pintype "passive"))
      (node (ref "D1") (pin "10") (pinfunction "G_10") (pintype "passive"))
      (node (ref "D2") (pin "10") (pinfunction "G_10") (pintype "passive"))
      (node (ref "D3") (pin "10") (pinfunction "G_10") (pintype "passive"))
      (node (ref "D4") (pin "10") (pinfunction "G_10") (pintype "passive"))
      (node (ref "D5") (pin "10") (pinfunction "G_10") (pintype "passive"))
      (node (ref "D6") (pin "10") (pinfunction "G_10") (pintype "passive"))
      (node (ref "D7") (pin "10") (pinfunction "G_10") (pintype "passive"))
      (node (ref "D8") (pin "10") (pinfunction "G_10") (pintype "passive"))
      (node (ref "D9") (pin "10") (pinfunction "G_10") (pintype "passive"))
      (node (ref "R22") (pin "2") (pinfunction "2_2") (pintype "passive"))
    )
    (net (code "9") (name "/IN_SEG_P") (class "Default")
      (node (ref "D0") (pin "5") (pinfunction "DP_5") (pintype "passive"))
      (node (ref "D1") (pin "5") (pinfunction "DP_5") (pintype "passive"))
      (node (ref "D2") (pin "5") (pinfunction "DP_5") (pintype "passive"))
      (node (ref "D3") (pin "5") (pinfunction "DP_5") (pintype "passive"))
      (node (ref "D4") (pin "5") (pinfunction "DP_5") (pintype "passive"))
      (node (ref "D5") (pin "5") (pinfunction "DP_5") (pintype "passive"))
      (node (ref "D6") (pin "5") (pinfunction "DP_5") (pintype "passive"))
      (node (ref "D7") (pin "5") (pinfunction "DP_5") (pintype "passive"))
      (node (ref "D8") (pin "5") (pinfunction "DP_5") (pintype "passive"))
      (node (ref "D9") (pin "5") (pinfunction "DP_5") (pintype "passive"))
      (node (ref "R23") (pin "2") (pinfunction "2_2") (pintype "passive"))
    )
    (net (code "10") (name "ADDR_A") (class "Default")
      (node (ref "IC1") (pin "10") (pinfunction "A_10") (pintype "input"))
      (node (ref "IC2") (pin "10") (pinfunction "A_10") (pintype "input"))
      (node (ref "IC3") (pin "10") (pinfunction "A_10") (pintype "input"))
      (node (ref "IC4") (pin "10") (pinfunction "A_10") (pintype "input"))
      (node (ref "IC5") (pin "10") (pinfunction "A_10") (pintype "input"))
      (node (ref "U$1") (pin "2-OUT2") (pinfunction "2-OUT2_2-OUT2") (pintype "bidirectional"))
    )
    (net (code "11") (name "ADDR_B") (class "Default")
      (node (ref "IC1") (pin "11") (pinfunction "B_11") (pintype "input"))
      (node (ref "IC2") (pin "11") (pinfunction "B_11") (pintype "input"))
      (node (ref "IC3") (pin "11") (pinfunction "B_11") (pintype "input"))
      (node (ref "IC4") (pin "11") (pinfunction "B_11") (pintype "input"))
      (node (ref "IC5") (pin "11") (pinfunction "B_11") (pintype "input"))
      (node (ref "U$1") (pin "3-LRCLK2") (pinfunction "3-LRCLK2_3-LRCLK2") (pintype "bidirectional"))
    )
    (net (code "12") (name "ADDR_C") (class "Default")
      (node (ref "IC1") (pin "14") (pinfunction "C_14") (pintype "input"))
      (node (ref "IC2") (pin "14") (pinfunction "C_14") (pintype "input"))
      (node (ref "IC3") (pin "14") (pinfunction "C_14") (pintype "input"))
      (node (ref "IC4") (pin "14") (pinfunction "C_14") (pintype "input"))
      (node (ref "IC5") (pin "14") (pinfunction "C_14") (pintype "input"))
      (node (ref "U$1") (pin "4-BCLK2") (pinfunction "4-BCLK2_4-BCLK2") (pintype "bidirectional"))
    )
    (net (code "13") (name "ADDR_D") (class "Default")
      (node (ref "IC1") (pin "13") (pinfunction "D_13") (pintype "input"))
      (node (ref "IC2") (pin "13") (pinfunction "D_13") (pintype "input"))
      (node (ref "IC3") (pin "13") (pinfunction "D_13") (pintype "input"))
      (node (ref "IC4") (pin "13") (pinfunction "D_13") (pintype "input"))
      (node (ref "IC5") (pin "13") (pinfunction "D_13") (pintype "input"))
      (node (ref "U$1") (pin "5-IN2") (pinfunction "5-IN2_5-IN2") (pintype "bidirectional"))
    )
    (net (code "14") (name "FADER_INH") (class "Default")
      (node (ref "IC1") (pin "15") (pinfunction "INH_15") (pintype "input"))
      (node (ref "U$1") (pin "6-OUT1D") (pinfunction "6-OUT1D_6-OUT1D") (pintype "bidirectional"))
    )
    (net (code "15") (name "FADER_X") (class "Default")
      (node (ref "IC1") (pin "1") (pinfunction "X_1") (pintype "output"))
      (node (ref "U$1") (pin "14-A0/TX3/SPDIF_OUT") (pinfunction "14-A0/TX3/SPDIF_OUT_14-A0/TX3/SPDIF_OUT") (pintype "bidirectional"))
    )
    (net (code "16") (name "GND") (class "Default")
      (node (ref "IC1") (pin "12") (pinfunction "VSS_12") (pintype "power_in"))
      (node (ref "IC2") (pin "12") (pinfunction "VSS_12") (pintype "power_in"))
      (node (ref "IC3") (pin "12") (pinfunction "VSS_12") (pintype "power_in"))
      (node (ref "IC4") (pin "12") (pinfunction "VSS_12") (pintype "power_in"))
      (node (ref "IC5") (pin "12") (pinfunction "VSS_12") (pintype "power_in"))
      (node (ref "LED0") (pin "K") (pinfunction "C_K") (pintype "passive"))
      (node (ref "LED1") (pin "K") (pinfunction "C_K") (pintype "passive"))
      (node (ref "LED2") (pin "K") (pinfunction "C_K") (pintype "passive"))
      (node (ref "LED3") (pin "K") (pinfunction "C_K") (pintype "passive"))
      (node (ref "LED4") (pin "K") (pinfunction "C_K") (pintype "passive"))
      (node (ref "LED5") (pin "K") (pinfunction "C_K") (pintype "passive"))
      (node (ref "LED6") (pin "K") (pinfunction "C_K") (pintype "passive"))
      (node (ref "LED7") (pin "K") (pinfunction "C_K") (pintype "passive"))
      (node (ref "LED8") (pin "K") (pinfunction "C_K") (pintype "passive"))
      (node (ref "LED9") (pin "K") (pinfunction "C_K") (pintype "passive"))
      (node (ref "M0") (pin "1") (pinfunction "1_1") (pintype "bidirectional"))
      (node (ref "M1") (pin "1") (pinfunction "1_1") (pintype "bidirectional"))
      (node (ref "P0_0") (pin "1") (pinfunction "A_1") (pintype "passive"))
      (node (ref "P0_1") (pin "1") (pinfunction "A_1") (pintype "passive"))
      (node (ref "P0_2") (pin "1") (pinfunction "A_1") (pintype "passive"))
      (node (ref "P0_3") (pin "1") (pinfunction "A_1") (pintype "passive"))
      (node (ref "P0_4") (pin "1") (pinfunction "A_1") (pintype "passive"))
      (node (ref "P0_5") (pin "1") (pinfunction "A_1") (pintype "passive"))
      (node (ref "P0_6") (pin "1") (pinfunction "A_1") (pintype "passive"))
      (node (ref "P0_7") (pin "1") (pinfunction "A_1") (pintype "passive"))
      (node (ref "P0_8") (pin "1") (pinfunction "A_1") (pintype "passive"))
      (node (ref "P0_9") (pin "1") (pinfunction "A_1") (pintype "passive"))
      (node (ref "P1_0") (pin "1") (pinfunction "A_1") (pintype "passive"))
      (node (ref "P1_1") (pin "1") (pinfunction "A_1") (pintype "passive"))
      (node (ref "P1_2") (pin "1") (pinfunction "A_1") (pintype "passive"))
      (node (ref "P1_3") (pin "1") (pinfunction "A_1") (pintype "passive"))
      (node (ref "P1_4") (pin "1") (pinfunction "A_1") (pintype "passive"))
      (node (ref "P1_5") (pin "1") (pinfunction "A_1") (pintype "passive"))
      (node (ref "P1_6") (pin "1") (pinfunction "A_1") (pintype "passive"))
      (node (ref "P1_7") (pin "1") (pinfunction "A_1") (pintype "passive"))
      (node (ref "P1_8") (pin "1") (pinfunction "A_1") (pintype "passive"))
      (node (ref "P1_9") (pin "1") (pinfunction "A_1") (pintype "passive"))
      (node (ref "R1") (pin "1") (pinfunction "1_1") (pintype "passive"))
      (node (ref "R10") (pin "1") (pinfunction "1_1") (pintype "passive"))
      (node (ref "R2") (pin "1") (pinfunction "1_1") (pintype "passive"))
      (node (ref "R29") (pin "1") (pinfunction "1_1") (pintype "passive"))
      (node (ref "R3") (pin "1") (pinfunction "1_1") (pintype "passive"))
      (node (ref "R30") (pin "1") (pinfunction "1_1") (pintype "passive"))
      (node (ref "R31") (pin "1") (pinfunction "1_1") (pintype "passive"))
      (node (ref "R32") (pin "1") (pinfunction "1_1") (pintype "passive"))
      (node (ref "R33") (pin "1") (pinfunction "1_1") (pintype "passive"))
      (node (ref "R34") (pin "1") (pinfunction "1_1") (pintype "passive"))
      (node (ref "R35") (pin "1") (pinfunction "1_1") (pintype "passive"))
      (node (ref "R36") (pin "1") (pinfunction "1_1") (pintype "passive"))
      (node (ref "R37") (pin "1") (pinfunction "1_1") (pintype "passive"))
      (node (ref "R38") (pin "1") (pinfunction "1_1") (pintype "passive"))
      (node (ref "R4") (pin "1") (pinfunction "1_1") (pintype "passive"))
      (node (ref "R5") (pin "1") (pinfunction "1_1") (pintype "passive"))
      (node (ref "R6") (pin "1") (pinfunction "1_1") (pintype "passive"))
      (node (ref "R7") (pin "1") (pinfunction "1_1") (pintype "passive"))
      (node (ref "R8") (pin "1") (pinfunction "1_1") (pintype "passive"))
      (node (ref "R9") (pin "1") (pinfunction "1_1") (pintype "passive"))
      (node (ref "S0") (pin "1") (pinfunction "1_1") (pintype "bidirectional"))
      (node (ref "S1") (pin "1") (pinfunction "1_1") (pintype "bidirectional"))
      (node (ref "S2") (pin "1") (pinfunction "1_1") (pintype "bidirectional"))
      (node (ref "S3") (pin "1") (pinfunction "1_1") (pintype "bidirectional"))
      (node (ref "S4") (pin "1") (pinfunction "1_1") (pintype "bidirectional"))
      (node (ref "S5") (pin "1") (pinfunction "1_1") (pintype "bidirectional"))
      (node (ref "S6") (pin "1") (pinfunction "1_1") (pintype "bidirectional"))
      (node (ref "S7") (pin "1") (pinfunction "1_1") (pintype "bidirectional"))
      (node (ref "T1") (pin "1") (pinfunction "E_1") (pintype "passive"))
      (node (ref "T10") (pin "1") (pinfunction "E_1") (pintype "passive"))
      (node (ref "T2") (pin "1") (pinfunction "E_1") (pintype "passive"))
      (node (ref "T3") (pin "1") (pinfunction "E_1") (pintype "passive"))
      (node (ref "T4") (pin "1") (pinfunction "E_1") (pintype "passive"))
      (node (ref "T5") (pin "1") (pinfunction "E_1") (pintype "passive"))
      (node (ref "T6") (pin "1") (pinfunction "E_1") (pintype "passive"))
      (node (ref "T7") (pin "1") (pinfunction "E_1") (pintype "passive"))
      (node (ref "T8") (pin "1") (pinfunction "E_1") (pintype "passive"))
      (node (ref "T9") (pin "1") (pinfunction "E_1") (pintype "passive"))
      (node (ref "U$1") (pin "GND1") (pinfunction "GND1_GND1") (pintype "bidirectional"))
    )
    (net (code "17") (name "LED0") (class "Default")
      (node (ref "R40") (pin "2") (pinfunction "2_2") (pintype "passive"))
      (node (ref "U$1") (pin "0-RX1/CS1/CRX2") (pinfunction "0-RX1/CS1/CRX2_0-RX1/CS1/CRX2") (pintype "bidirectional"))
    )
    (net (code "18") (name "LED1") (class "Default")
      (node (ref "R39") (pin "2") (pinfunction "2_2") (pintype "passive"))
      (node (ref "U$1") (pin "1-TX1/MISO1/CTX2") (pinfunction "1-TX1/MISO1/CTX2_1-TX1/MISO1/CTX2") (pintype "bidirectional"))
    )
    (net (code "19") (name "LED2") (class "Default")
      (node (ref "R41") (pin "2") (pinfunction "2_2") (pintype "passive"))
      (node (ref "U$1") (pin "35-TX8") (pinfunction "35/TX8_35-TX8") (pintype "bidirectional"))
    )
    (net (code "20") (name "LED3") (class "Default")
      (node (ref "R42") (pin "2") (pinfunction "2_2") (pintype "passive"))
      (node (ref "U$1") (pin "11-MOSI/CTX1") (pinfunction "11-MOSI/CTX1_11-MOSI/CTX1") (pintype "bidirectional"))
    )
    (net (code "21") (name "LED4") (class "Default")
      (node (ref "R43") (pin "2") (pinfunction "2_2") (pintype "passive"))
      (node (ref "U$1") (pin "12-MISO/MQSL") (pinfunction "12-MISO/MQSL_12-MISO/MQSL") (pintype "bidirectional"))
    )
    (net (code "22") (name "LED5") (class "Default")
      (node (ref "R44") (pin "2") (pinfunction "2_2") (pintype "passive"))
      (node (ref "U$1") (pin "13-SCK/LED") (pinfunction "13-SCK/LED_13-SCK/LED") (pintype "bidirectional"))
    )
    (net (code "23") (name "LED6") (class "Default")
      (node (ref "R45") (pin "2") (pinfunction "2_2") (pintype "passive"))
      (node (ref "U$1") (pin "32-OUT1B") (pinfunction "32-OUT1B_32-OUT1B") (pintype "bidirectional"))
    )
    (net (code "24") (name "LED7") (class "Default")
      (node (ref "R46") (pin "2") (pinfunction "2_2") (pintype "passive"))
      (node (ref "U$1") (pin "33-MCLK2") (pinfunction "33-MCLK2_33-MCLK2") (pintype "bidirectional"))
    )
    (net (code "25") (name "LED8") (class "Default")
      (node (ref "R47") (pin "2") (pinfunction "2_2") (pintype "passive"))
      (node (ref "U$1") (pin "36-PWM") (pinfunction "36-PWM_36-PWM") (pintype "bidirectional"))
    )
    (net (code "26") (name "LED9") (class "Default")
      (node (ref "R48") (pin "2") (pinfunction "2_2") (pintype "passive"))
      (node (ref "U$1") (pin "37-PWM") (pinfunction "37-PWM_37-PWM") (pintype "bidirectional"))
    )
    (net (code "27") (name "Net-(IC1A-X0)") (class "Default")
      (node (ref "IC1") (pin "9") (pinfunction "X0_9") (pintype "input"))
      (node (ref "M1") (pin "2") (pinfunction "2_2") (pintype "bidirectional"))
    )
    (net (code "28") (name "Net-(IC1A-X1)") (class "Default")
      (node (ref "IC1") (pin "8") (pinfunction "X1_8") (pintype "input"))
      (node (ref "M0") (pin "2") (pinfunction "2_2") (pintype "bidirectional"))
    )
    (net (code "29") (name "Net-(IC1A-X2)") (class "Default")
      (node (ref "IC1") (pin "7") (pinfunction "X2_7") (pintype "input"))
      (node (ref "S7") (pin "2") (pinfunction "2_2") (pintype "bidirectional"))
    )
    (net (code "30") (name "Net-(IC1A-X3)") (class "Default")
      (node (ref "IC1") (pin "6") (pinfunction "X3_6") (pintype "input"))
      (node (ref "S6") (pin "2") (pinfunction "2_2") (pintype "bidirectional"))
    )
    (net (code "31") (name "Net-(IC1A-X4)") (class "Default")
      (node (ref "IC1") (pin "5") (pinfunction "X4_5") (pintype "input"))
      (node (ref "S5") (pin "2") (pinfunction "2_2") (pintype "bidirectional"))
    )
    (net (code "32") (name "Net-(IC1A-X5)") (class "Default")
      (node (ref "IC1") (pin "4") (pinfunction "X5_4") (pintype "input"))
      (node (ref "S4") (pin "2") (pinfunction "2_2") (pintype "bidirectional"))
    )
    (net (code "33") (name "Net-(IC1A-X6)") (class "Default")
      (node (ref "IC1") (pin "3") (pinfunction "X6_3") (pintype "input"))
      (node (ref "S3") (pin "2") (pinfunction "2_2") (pintype "bidirectional"))
    )
    (net (code "34") (name "Net-(IC1A-X7)") (class "Default")
      (node (ref "IC1") (pin "2") (pinfunction "X7_2") (pintype "input"))
      (node (ref "S2") (pin "2") (pinfunction "2_2") (pintype "bidirectional"))
    )
    (net (code "35") (name "Net-(IC1A-X8)") (class "Default")
      (node (ref "IC1") (pin "23") (pinfunction "X8_23") (pintype "input"))
      (node (ref "S1") (pin "2") (pinfunction "2_2") (pintype "bidirectional"))
    )
    (net (code "36") (name "Net-(IC1A-X9)") (class "Default")
      (node (ref "IC1") (pin "22") (pinfunction "X9_22") (pintype "input"))
      (node (ref "S0") (pin "2") (pinfunction "2_2") (pintype "bidirectional"))
    )
    (net (code "37") (name "Net-(IC2A-X0)") (class "Default")
      (node (ref "IC2") (pin "9") (pinfunction "X0_9") (pintype "input"))
      (node (ref "SW9") (pin "4") (pinfunction "P1_4") (pintype "passive"))
    )
    (net (code "38") (name "Net-(IC2A-X1)") (class "Default")
      (node (ref "IC2") (pin "8") (pinfunction "X1_8") (pintype "input"))
      (node (ref "SW8") (pin "4") (pinfunction "P1_4") (pintype "passive"))
    )
    (net (code "39") (name "Net-(IC2A-X2)") (class "Default")
      (node (ref "IC2") (pin "7") (pinfunction "X2_7") (pintype "input"))
      (node (ref "SW7") (pin "4") (pinfunction "P1_4") (pintype "passive"))
    )
    (net (code "40") (name "Net-(IC2A-X3)") (class "Default")
      (node (ref "IC2") (pin "6") (pinfunction "X3_6") (pintype "input"))
      (node (ref "SW6") (pin "4") (pinfunction "P1_4") (pintype "passive"))
    )
    (net (code "41") (name "Net-(IC2A-X4)") (class "Default")
      (node (ref "IC2") (pin "5") (pinfunction "X4_5") (pintype "input"))
      (node (ref "SW5") (pin "4") (pinfunction "P1_4") (pintype "passive"))
    )
    (net (code "42") (name "Net-(IC2A-X5)") (class "Default")
      (node (ref "IC2") (pin "4") (pinfunction "X5_4") (pintype "input"))
      (node (ref "SW4") (pin "4") (pinfunction "P1_4") (pintype "passive"))
    )
    (net (code "43") (name "Net-(IC2A-X6)") (class "Default")
      (node (ref "IC2") (pin "3") (pinfunction "X6_3") (pintype "input"))
      (node (ref "SW3") (pin "4") (pinfunction "P1_4") (pintype "passive"))
    )
    (net (code "44") (name "Net-(IC2A-X7)") (class "Default")
      (node (ref "IC2") (pin "2") (pinfunction "X7_2") (pintype "input"))
      (node (ref "SW2") (pin "4") (pinfunction "P1_4") (pintype "passive"))
    )
    (net (code "45") (name "Net-(IC2A-X8)") (class "Default")
      (node (ref "IC2") (pin "23") (pinfunction "X8_23") (pintype "input"))
      (node (ref "SW1") (pin "4") (pinfunction "P1_4") (pintype "passive"))
    )
    (net (code "46") (name "Net-(IC2A-X9)") (class "Default")
      (node (ref "IC2") (pin "22") (pinfunction "X9_22") (pintype "input"))
      (node (ref "SW0") (pin "4") (pinfunction "P1_4") (pintype "passive"))
    )
    (net (code "47") (name "Net-(IC3A-X0)") (class "Default")
      (node (ref "IC3") (pin "9") (pinfunction "X0_9") (pintype "input"))
      (node (ref "P0_9") (pin "2") (pinfunction "S_2") (pintype "passive"))
    )
    (net (code "48") (name "Net-(IC3A-X1)") (class "Default")
      (node (ref "IC3") (pin "8") (pinfunction "X1_8") (pintype "input"))
      (node (ref "P0_8") (pin "2") (pinfunction "S_2") (pintype "passive"))
    )
    (net (code "49") (name "Net-(IC3A-X2)") (class "Default")
      (node (ref "IC3") (pin "7") (pinfunction "X2_7") (pintype "input"))
      (node (ref "P0_7") (pin "2") (pinfunction "S_2") (pintype "passive"))
    )
    (net (code "50") (name "Net-(IC3A-X3)") (class "Default")
      (node (ref "IC3") (pin "6") (pinfunction "X3_6") (pintype "input"))
      (node (ref "P0_6") (pin "2") (pinfunction "S_2") (pintype "passive"))
    )
    (net (code "51") (name "Net-(IC3A-X4)") (class "Default")
      (node (ref "IC3") (pin "5") (pinfunction "X4_5") (pintype "input"))
      (node (ref "P0_5") (pin "2") (pinfunction "S_2") (pintype "passive"))
    )
    (net (code "52") (name "Net-(IC3A-X5)") (class "Default")
      (node (ref "IC3") (pin "4") (pinfunction "X5_4") (pintype "input"))
      (node (ref "P0_4") (pin "2") (pinfunction "S_2") (pintype "passive"))
    )
    (net (code "53") (name "Net-(IC3A-X6)") (class "Default")
      (node (ref "IC3") (pin "3") (pinfunction "X6_3") (pintype "input"))
      (node (ref "P0_3") (pin "2") (pinfunction "S_2") (pintype "passive"))
    )
    (net (code "54") (name "Net-(IC3A-X7)") (class "Default")
      (node (ref "IC3") (pin "2") (pinfunction "X7_2") (pintype "input"))
      (node (ref "P0_2") (pin "2") (pinfunction "S_2") (pintype "passive"))
    )
    (net (code "55") (name "Net-(IC3A-X8)") (class "Default")
      (node (ref "IC3") (pin "23") (pinfunction "X8_23") (pintype "input"))
      (node (ref "P0_1") (pin "2") (pinfunction "S_2") (pintype "passive"))
    )
    (net (code "56") (name "Net-(IC3A-X9)") (class "Default")
      (node (ref "IC3") (pin "22") (pinfunction "X9_22") (pintype "input"))
      (node (ref "P0_0") (pin "2") (pinfunction "S_2") (pintype "passive"))
    )
    (net (code "57") (name "Net-(IC4A-X0)") (class "Default")
      (node (ref "IC4") (pin "9") (pinfunction "X0_9") (pintype "input"))
      (node (ref "P1_9") (pin "2") (pinfunction "S_2") (pintype "passive"))
    )
    (net (code "58") (name "Net-(IC4A-X1)") (class "Default")
      (node (ref "IC4") (pin "8") (pinfunction "X1_8") (pintype "input"))
      (node (ref "P1_8") (pin "2") (pinfunction "S_2") (pintype "passive"))
    )
    (net (code "59") (name "Net-(IC4A-X2)") (class "Default")
      (node (ref "IC4") (pin "7") (pinfunction "X2_7") (pintype "input"))
      (node (ref "P1_7") (pin "2") (pinfunction "S_2") (pintype "passive"))
    )
    (net (code "60") (name "Net-(IC4A-X3)") (class "Default")
      (node (ref "IC4") (pin "6") (pinfunction "X3_6") (pintype "input"))
      (node (ref "P1_6") (pin "2") (pinfunction "S_2") (pintype "passive"))
    )
    (net (code "61") (name "Net-(IC4A-X4)") (class "Default")
      (node (ref "IC4") (pin "5") (pinfunction "X4_5") (pintype "input"))
      (node (ref "P1_5") (pin "2") (pinfunction "S_2") (pintype "passive"))
    )
    (net (code "62") (name "Net-(IC4A-X5)") (class "Default")
      (node (ref "IC4") (pin "4") (pinfunction "X5_4") (pintype "input"))
      (node (ref "P1_4") (pin "2") (pinfunction "S_2") (pintype "passive"))
    )
    (net (code "63") (name "Net-(IC4A-X6)") (class "Default")
      (node (ref "IC4") (pin "3") (pinfunction "X6_3") (pintype "input"))
      (node (ref "P1_3") (pin "2") (pinfunction "S_2") (pintype "passive"))
    )
    (net (code "64") (name "Net-(IC4A-X7)") (class "Default")
      (node (ref "IC4") (pin "2") (pinfunction "X7_2") (pintype "input"))
      (node (ref "P1_2") (pin "2") (pinfunction "S_2") (pintype "passive"))
    )
    (net (code "65") (name "Net-(IC4A-X8)") (class "Default")
      (node (ref "IC4") (pin "23") (pinfunction "X8_23") (pintype "input"))
      (node (ref "P1_1") (pin "2") (pinfunction "S_2") (pintype "passive"))
    )
    (net (code "66") (name "Net-(IC4A-X9)") (class "Default")
      (node (ref "IC4") (pin "22") (pinfunction "X9_22") (pintype "input"))
      (node (ref "P1_0") (pin "2") (pinfunction "S_2") (pintype "passive"))
    )
    (net (code "67") (name "Net-(IC5A-X0)") (class "Default")
      (node (ref "IC5") (pin "9") (pinfunction "X0_9") (pintype "input"))
      (node (ref "MS9") (pin "4") (pinfunction "P1_4") (pintype "passive"))
    )
    (net (code "68") (name "Net-(IC5A-X1)") (class "Default")
      (node (ref "IC5") (pin "8") (pinfunction "X1_8") (pintype "input"))
      (node (ref "MS8") (pin "4") (pinfunction "P1_4") (pintype "passive"))
    )
    (net (code "69") (name "Net-(IC5A-X2)") (class "Default")
      (node (ref "IC5") (pin "7") (pinfunction "X2_7") (pintype "input"))
      (node (ref "MS7") (pin "4") (pinfunction "P1_4") (pintype "passive"))
    )
    (net (code "70") (name "Net-(IC5A-X3)") (class "Default")
      (node (ref "IC5") (pin "6") (pinfunction "X3_6") (pintype "input"))
      (node (ref "MS6") (pin "4") (pinfunction "P1_4") (pintype "passive"))
    )
    (net (code "71") (name "Net-(IC5A-X4)") (class "Default")
      (node (ref "IC5") (pin "5") (pinfunction "X4_5") (pintype "input"))
      (node (ref "MS5") (pin "4") (pinfunction "P1_4") (pintype "passive"))
    )
    (net (code "72") (name "Net-(IC5A-X5)") (class "Default")
      (node (ref "IC5") (pin "4") (pinfunction "X5_4") (pintype "input"))
      (node (ref "MS4") (pin "4") (pinfunction "P1_4") (pintype "passive"))
    )
    (net (code "73") (name "Net-(IC5A-X6)") (class "Default")
      (node (ref "IC5") (pin "3") (pinfunction "X6_3") (pintype "input"))
      (node (ref "MS3") (pin "4") (pinfunction "P1_4") (pintype "passive"))
    )
    (net (code "74") (name "Net-(IC5A-X7)") (class "Default")
      (node (ref "IC5") (pin "2") (pinfunction "X7_2") (pintype "input"))
      (node (ref "MS2") (pin "4") (pinfunction "P1_4") (pintype "passive"))
    )
    (net (code "75") (name "Net-(IC5A-X8)") (class "Default")
      (node (ref "IC5") (pin "23") (pinfunction "X8_23") (pintype "input"))
      (node (ref "MS1") (pin "4") (pinfunction "P1_4") (pintype "passive"))
    )
    (net (code "76") (name "Net-(IC5A-X9)") (class "Default")
      (node (ref "IC5") (pin "22") (pinfunction "X9_22") (pintype "input"))
      (node (ref "MS0") (pin "4") (pinfunction "P1_4") (pintype "passive"))
    )
    (net (code "77") (name "Net-(LED0-PadA)") (class "Default")
      (node (ref "LED0") (pin "A") (pinfunction "A_A") (pintype "passive"))
      (node (ref "R40") (pin "1") (pinfunction "1_1") (pintype "passive"))
    )
    (net (code "78") (name "Net-(LED1-PadA)") (class "Default")
      (node (ref "LED1") (pin "A") (pinfunction "A_A") (pintype "passive"))
      (node (ref "R39") (pin "1") (pinfunction "1_1") (pintype "passive"))
    )
    (net (code "79") (name "Net-(LED2-PadA)") (class "Default")
      (node (ref "LED2") (pin "A") (pinfunction "A_A") (pintype "passive"))
      (node (ref "R41") (pin "1") (pinfunction "1_1") (pintype "passive"))
    )
    (net (code "80") (name "Net-(LED3-PadA)") (class "Default")
      (node (ref "LED3") (pin "A") (pinfunction "A_A") (pintype "passive"))
      (node (ref "R42") (pin "1") (pinfunction "1_1") (pintype "passive"))
    )
    (net (code "81") (name "Net-(LED4-PadA)") (class "Default")
      (node (ref "LED4") (pin "A") (pinfunction "A_A") (pintype "passive"))
      (node (ref "R43") (pin "1") (pinfunction "1_1") (pintype "passive"))
    )
    (net (code "82") (name "Net-(LED5-PadA)") (class "Default")
      (node (ref "LED5") (pin "A") (pinfunction "A_A") (pintype "passive"))
      (node (ref "R44") (pin "1") (pinfunction "1_1") (pintype "passive"))
    )
    (net (code "83") (name "Net-(LED6-PadA)") (class "Default")
      (node (ref "LED6") (pin "A") (pinfunction "A_A") (pintype "passive"))
      (node (ref "R45") (pin "1") (pinfunction "1_1") (pintype "passive"))
    )
    (net (code "84") (name "Net-(LED7-PadA)") (class "Default")
      (node (ref "LED7") (pin "A") (pinfunction "A_A") (pintype "passive"))
      (node (ref "R46") (pin "1") (pinfunction "1_1") (pintype "passive"))
    )
    (net (code "85") (name "Net-(LED8-PadA)") (class "Default")
      (node (ref "LED8") (pin "A") (pinfunction "A_A") (pintype "passive"))
      (node (ref "R47") (pin "1") (pinfunction "1_1") (pintype "passive"))
    )
    (net (code "86") (name "Net-(LED9-PadA)") (class "Default")
      (node (ref "LED9") (pin "A") (pinfunction "A_A") (pintype "passive"))
      (node (ref "R48") (pin "1") (pinfunction "1_1") (pintype "passive"))
    )
    (net (code "87") (name "Net-(MS0-P)") (class "Default")
      (node (ref "MS0") (pin "3") (pinfunction "P_3") (pintype "passive"))
      (node (ref "R29") (pin "2") (pinfunction "2_2") (pintype "passive"))
    )
    (net (code "88") (name "Net-(MS1-P)") (class "Default")
      (node (ref "MS1") (pin "3") (pinfunction "P_3") (pintype "passive"))
      (node (ref "R30") (pin "2") (pinfunction "2_2") (pintype "passive"))
    )
    (net (code "89") (name "Net-(MS2-P)") (class "Default")
      (node (ref "MS2") (pin "3") (pinfunction "P_3") (pintype "passive"))
      (node (ref "R31") (pin "2") (pinfunction "2_2") (pintype "passive"))
    )
    (net (code "90") (name "Net-(MS3-P)") (class "Default")
      (node (ref "MS3") (pin "3") (pinfunction "P_3") (pintype "passive"))
      (node (ref "R32") (pin "2") (pinfunction "2_2") (pintype "passive"))
    )
    (net (code "91") (name "Net-(MS4-P)") (class "Default")
      (node (ref "MS4") (pin "3") (pinfunction "P_3") (pintype "passive"))
      (node (ref "R38") (pin "2") (pinfunction "2_2") (pintype "passive"))
    )
    (net (code "92") (name "Net-(MS5-P)") (class "Default")
      (node (ref "MS5") (pin "3") (pinfunction "P_3") (pintype "passive"))
      (node (ref "R33") (pin "2") (pinfunction "2_2") (pintype "passive"))
    )
    (net (code "93") (name "Net-(MS6-P)") (class "Default")
      (node (ref "MS6") (pin "3") (pinfunction "P_3") (pintype "passive"))
      (node (ref "R34") (pin "2") (pinfunction "2_2") (pintype "passive"))
    )
    (net (code "94") (name "Net-(MS7-P)") (class "Default")
      (node (ref "MS7") (pin "3") (pinfunction "P_3") (pintype "passive"))
      (node (ref "R35") (pin "2") (pinfunction "2_2") (pintype "passive"))
    )
    (net (code "95") (name "Net-(MS8-P)") (class "Default")
      (node (ref "MS8") (pin "3") (pinfunction "P_3") (pintype "passive"))
      (node (ref "R36") (pin "2") (pinfunction "2_2") (pintype "passive"))
    )
    (net (code "96") (name "Net-(MS9-P)") (class "Default")
      (node (ref "MS9") (pin "3") (pinfunction "P_3") (pintype "passive"))
      (node (ref "R37") (pin "2") (pinfunction "2_2") (pintype "passive"))
    )
    (net (code "97") (name "Net-(SW0-P)") (class "Default")
      (node (ref "R1") (pin "2") (pinfunction "2_2") (pintype "passive"))
      (node (ref "SW0") (pin "3") (pinfunction "P_3") (pintype "passive"))
    )
    (net (code "98") (name "Net-(SW1-P)") (class "Default")
      (node (ref "R2") (pin "2") (pinfunction "2_2") (pintype "passive"))
      (node (ref "SW1") (pin "3") (pinfunction "P_3") (pintype "passive"))
    )
    (net (code "99") (name "Net-(SW2-P)") (class "Default")
      (node (ref "R3") (pin "2") (pinfunction "2_2") (pintype "passive"))
      (node (ref "SW2") (pin "3") (pinfunction "P_3") (pintype "passive"))
    )
    (net (code "100") (name "Net-(SW3-P)") (class "Default")
      (node (ref "R4") (pin "2") (pinfunction "2_2") (pintype "passive"))
      (node (ref "SW3") (pin "3") (pinfunction "P_3") (pintype "passive"))
    )
    (net (code "101") (name "Net-(SW4-P)") (class "Default")
      (node (ref "R10") (pin "2") (pinfunction "2_2") (pintype "passive"))
      (node (ref "SW4") (pin "3") (pinfunction "P_3") (pintype "passive"))
    )
    (net (code "102") (name "Net-(SW5-P)") (class "Default")
      (node (ref "R5") (pin "2") (pinfunction "2_2") (pintype "passive"))
      (node (ref "SW5") (pin "3") (pinfunction "P_3") (pintype "passive"))
    )
    (net (code "103") (name "Net-(SW6-P)") (class "Default")
      (node (ref "R6") (pin "2") (pinfunction "2_2") (pintype "passive"))
      (node (ref "SW6") (pin "3") (pinfunction "P_3") (pintype "passive"))
    )
    (net (code "104") (name "Net-(SW7-P)") (class "Default")
      (node (ref "R7") (pin "2") (pinfunction "2_2") (pintype "passive"))
      (node (ref "SW7") (pin "3") (pinfunction "P_3") (pintype "passive"))
    )
    (net (code "105") (name "Net-(SW8-P)") (class "Default")
      (node (ref "R8") (pin "2") (pinfunction "2_2") (pintype "passive"))
      (node (ref "SW8") (pin "3") (pinfunction "P_3") (pintype "passive"))
    )
    (net (code "106") (name "Net-(SW9-P)") (class "Default")
      (node (ref "R9") (pin "2") (pinfunction "2_2") (pintype "passive"))
      (node (ref "SW9") (pin "3") (pinfunction "P_3") (pintype "passive"))
    )
    (net (code "107") (name "Net-(T1-B)") (class "Default")
      (node (ref "R11") (pin "2") (pinfunction "2_2") (pintype "passive"))
      (node (ref "T1") (pin "2") (pinfunction "B_2") (pintype "passive"))
    )
    (net (code "108") (name "Net-(T2-B)") (class "Default")
      (node (ref "R12") (pin "2") (pinfunction "2_2") (pintype "passive"))
      (node (ref "T2") (pin "2") (pinfunction "B_2") (pintype "passive"))
    )
    (net (code "109") (name "Net-(T3-B)") (class "Default")
      (node (ref "R13") (pin "2") (pinfunction "2_2") (pintype "passive"))
      (node (ref "T3") (pin "2") (pinfunction "B_2") (pintype "passive"))
    )
    (net (code "110") (name "Net-(T4-B)") (class "Default")
      (node (ref "R14") (pin "2") (pinfunction "2_2") (pintype "passive"))
      (node (ref "T4") (pin "2") (pinfunction "B_2") (pintype "passive"))
    )
    (net (code "111") (name "Net-(T5-B)") (class "Default")
      (node (ref "R15") (pin "2") (pinfunction "2_2") (pintype "passive"))
      (node (ref "T5") (pin "2") (pinfunction "B_2") (pintype "passive"))
    )
    (net (code "112") (name "Net-(T6-B)") (class "Default")
      (node (ref "R24") (pin "2") (pinfunction "2_2") (pintype "passive"))
      (node (ref "T6") (pin "2") (pinfunction "B_2") (pintype "passive"))
    )
    (net (code "113") (name "Net-(T7-B)") (class "Default")
      (node (ref "R25") (pin "2") (pinfunction "2_2") (pintype "passive"))
      (node (ref "T7") (pin "2") (pinfunction "B_2") (pintype "passive"))
    )
    (net (code "114") (name "Net-(T8-B)") (class "Default")
      (node (ref "R26") (pin "2") (pinfunction "2_2") (pintype "passive"))
      (node (ref "T8") (pin "2") (pinfunction "B_2") (pintype "passive"))
    )
    (net (code "115") (name "Net-(T9-B)") (class "Default")
      (node (ref "R27") (pin "2") (pinfunction "2_2") (pintype "passive"))
      (node (ref "T9") (pin "2") (pinfunction "B_2") (pintype "passive"))
    )
    (net (code "116") (name "Net-(T10-B)") (class "Default")
      (node (ref "R28") (pin "2") (pinfunction "2_2") (pintype "passive"))
      (node (ref "T10") (pin "2") (pinfunction "B_2") (pintype "passive"))
    )
    (net (code "117") (name "POT0_INH") (class "Default")
      (node (ref "IC3") (pin "15") (pinfunction "INH_15") (pintype "input"))
      (node (ref "U$1") (pin "8-TX2/IN1") (pinfunction "8-TX2/IN1_8-TX2/IN1") (pintype "bidirectional"))
    )
    (net (code "118") (name "POT0_X") (class "Default")
      (node (ref "IC3") (pin "1") (pinfunction "X_1") (pintype "output"))
      (node (ref "U$1") (pin "16-A2/RX4/SCL1") (pinfunction "16-A2/RX4/SCL1_16-A2/RX4/SCL1") (pintype "bidirectional"))
    )
    (net (code "119") (name "POT1_INH") (class "Default")
      (node (ref "IC4") (pin "15") (pinfunction "INH_15") (pintype "input"))
      (node (ref "U$1") (pin "9-OUT1C") (pinfunction "9-OUT1C_9-OUT1C") (pintype "bidirectional"))
    )
    (net (code "120") (name "POT1_X") (class "Default")
      (node (ref "IC4") (pin "1") (pinfunction "X_1") (pintype "output"))
      (node (ref "U$1") (pin "17-A3/TX4/SDA1") (pinfunction "17-A3/TX4/SDA1_17-A3/TX4/SDA1") (pintype "bidirectional"))
    )
    (net (code "121") (name "SEG_A") (class "Default")
      (node (ref "R16") (pin "1") (pinfunction "1_1") (pintype "passive"))
      (node (ref "U$1") (pin "39-A15/CS/OUT1A") (pinfunction "39-A15/CS/OUT1A_39-A15/CS/OUT1A") (pintype "bidirectional"))
    )
    (net (code "122") (name "SEG_B") (class "Default")
      (node (ref "R17") (pin "1") (pinfunction "1_1") (pintype "passive"))
      (node (ref "U$1") (pin "40-A16/CS1") (pinfunction "40-A16/CS1_40-A16/CS1") (pintype "bidirectional"))
    )
    (net (code "123") (name "SEG_C") (class "Default")
      (node (ref "R18") (pin "1") (pinfunction "1_1") (pintype "passive"))
      (node (ref "U$1") (pin "41-A17/MISO1") (pinfunction "41-A17/MISO1_41-A17/MISO1") (pintype "bidirectional"))
    )
    (net (code "124") (name "SEG_D") (class "Default")
      (node (ref "R19") (pin "1") (pinfunction "1_1") (pintype "passive"))
      (node (ref "U$1") (pin "30-CRX3") (pinfunction "30-CRX3_30-CRX3") (pintype "bidirectional"))
    )
    (net (code "125") (name "SEG_E") (class "Default")
      (node (ref "R20") (pin "1") (pinfunction "1_1") (pintype "passive"))
      (node (ref "U$1") (pin "31-CTX3") (pinfunction "31-CTX3_31-CTX3") (pintype "bidirectional"))
    )
    (net (code "126") (name "SEG_F") (class "Default")
      (node (ref "R21") (pin "1") (pinfunction "1_1") (pintype "passive"))
      (node (ref "U$1") (pin "28-RX7") (pinfunction "28-RX7_28-RX7") (pintype "bidirectional"))
    )
    (net (code "127") (name "SEG_G") (class "Default")
      (node (ref "R22") (pin "1") (pinfunction "1_1") (pintype "passive"))
      (node (ref "U$1") (pin "29-TX7") (pinfunction "29-TX7_29-TX7") (pintype "bidirectional"))
    )
    (net (code "128") (name "SEG_K0") (class "Default")
      (node (ref "R11") (pin "1") (pinfunction "1_1") (pintype "passive"))
      (node (ref "U$1") (pin "19-A5/SCL0") (pinfunction "19-A5/SCL0_19-A5/SCL0") (pintype "bidirectional"))
    )
    (net (code "129") (name "SEG_K1") (class "Default")
      (node (ref "R12") (pin "1") (pinfunction "1_1") (pintype "passive"))
      (node (ref "U$1") (pin "20-A6/TX5/LRCLK1") (pinfunction "20-A6/TX5/LRCLK1_20-A6/TX5/LRCLK1") (pintype "bidirectional"))
    )
    (net (code "130") (name "SEG_K1AA") (class "Default")
      (node (ref "D1") (pin "3") (pinfunction "CK1_3") (pintype "passive"))
      (node (ref "D1") (pin "8") (pinfunction "CK2_8") (pintype "passive"))
      (node (ref "T2") (pin "3") (pinfunction "C_3") (pintype "passive"))
    )
    (net (code "131") (name "SEG_K1AAAAV") (class "Default")
      (node (ref "D6") (pin "3") (pinfunction "CK1_3") (pintype "passive"))
      (node (ref "D6") (pin "8") (pinfunction "CK2_8") (pintype "passive"))
      (node (ref "T7") (pin "3") (pinfunction "C_3") (pintype "passive"))
    )
    (net (code "132") (name "SEG_K2") (class "Default")
      (node (ref "R13") (pin "1") (pinfunction "1_1") (pintype "passive"))
      (node (ref "U$1") (pin "21-A7/RX5/BCLK1") (pinfunction "21-A7/RX5/BCLK1_21-A7/RX5/BCLK1") (pintype "bidirectional"))
    )
    (net (code "133") (name "SEG_K2AA") (class "Default")
      (node (ref "D2") (pin "3") (pinfunction "CK1_3") (pintype "passive"))
      (node (ref "D2") (pin "8") (pinfunction "CK2_8") (pintype "passive"))
      (node (ref "T3") (pin "3") (pinfunction "C_3") (pintype "passive"))
    )
    (net (code "134") (name "SEG_K2VVV") (class "Default")
      (node (ref "D7") (pin "3") (pinfunction "CK1_3") (pintype "passive"))
      (node (ref "D7") (pin "8") (pinfunction "CK2_8") (pintype "passive"))
      (node (ref "T8") (pin "3") (pinfunction "C_3") (pintype "passive"))
    )
    (net (code "135") (name "SEG_K3") (class "Default")
      (node (ref "R14") (pin "1") (pinfunction "1_1") (pintype "passive"))
      (node (ref "U$1") (pin "22-A8/CTX1") (pinfunction "22-A8/CTX1_22-A8/CTX1") (pintype "bidirectional"))
    )
    (net (code "136") (name "SEG_K3AA") (class "Default")
      (node (ref "D3") (pin "3") (pinfunction "CK1_3") (pintype "passive"))
      (node (ref "D3") (pin "8") (pinfunction "CK2_8") (pintype "passive"))
      (node (ref "T4") (pin "3") (pinfunction "C_3") (pintype "passive"))
    )
    (net (code "137") (name "SEG_K3VVV") (class "Default")
      (node (ref "D8") (pin "3") (pinfunction "CK1_3") (pintype "passive"))
      (node (ref "D8") (pin "8") (pinfunction "CK2_8") (pintype "passive"))
      (node (ref "T9") (pin "3") (pinfunction "C_3") (pintype "passive"))
    )
    (net (code "138") (name "SEG_K4") (class "Default")
      (node (ref "R15") (pin "1") (pinfunction "1_1") (pintype "passive"))
      (node (ref "U$1") (pin "23-A9/CRX1/MCLK1") (pinfunction "23-A9/CRX1/MCLK1_23-A9/CRX1/MCLK1") (pintype "bidirectional"))
    )
    (net (code "139") (name "SEG_K4AA") (class "Default")
      (node (ref "D4") (pin "3") (pinfunction "CK1_3") (pintype "passive"))
      (node (ref "D4") (pin "8") (pinfunction "CK2_8") (pintype "passive"))
      (node (ref "T5") (pin "3") (pinfunction "C_3") (pintype "passive"))
    )
    (net (code "140") (name "SEG_K4VDF") (class "Default")
      (node (ref "D9") (pin "3") (pinfunction "CK1_3") (pintype "passive"))
      (node (ref "D9") (pin "8") (pinfunction "CK2_8") (pintype "passive"))
      (node (ref "T10") (pin "3") (pinfunction "C_3") (pintype "passive"))
    )
    (net (code "141") (name "SEG_K5") (class "Default")
      (node (ref "R24") (pin "1") (pinfunction "1_1") (pintype "passive"))
      (node (ref "U$1") (pin "24-A10/TX6/SCL2") (pinfunction "24-A10/TX6/SCL2_24-A10/TX6/SCL2") (pintype "bidirectional"))
    )
    (net (code "142") (name "SEG_K6") (class "Default")
      (node (ref "R25") (pin "1") (pinfunction "1_1") (pintype "passive"))
      (node (ref "U$1") (pin "25-A11/RX6/SDA2") (pinfunction "25-A11/RX6/SDA2_25-A11/RX6/SDA2") (pintype "bidirectional"))
    )
    (net (code "143") (name "SEG_K7") (class "Default")
      (node (ref "R26") (pin "1") (pinfunction "1_1") (pintype "passive"))
      (node (ref "U$1") (pin "26-A12/MOSI1") (pinfunction "26-A12/MOSI1_26-A12/MOSI1") (pintype "bidirectional"))
    )
    (net (code "144") (name "SEG_K8") (class "Default")
      (node (ref "R27") (pin "1") (pinfunction "1_1") (pintype "passive"))
      (node (ref "U$1") (pin "27-A13/SCK1") (pinfunction "27-A13/SCK1_27-A13/SCK1") (pintype "bidirectional"))
    )
    (net (code "145") (name "SEG_K9") (class "Default")
      (node (ref "R28") (pin "1") (pinfunction "1_1") (pintype "passive"))
      (node (ref "U$1") (pin "38-A14/CS/IN1") (pinfunction "38-A14/CS/IN1_38-A14/CS/IN1") (pintype "bidirectional"))
    )
    (net (code "146") (name "SEG_P") (class "Default")
      (node (ref "R23") (pin "1") (pinfunction "1_1") (pintype "passive"))
      (node (ref "U$1") (pin "34-RX8") (pinfunction "34-RX8_34-RX8") (pintype "bidirectional"))
    )
    (net (code "147") (name "SIG_K0AA") (class "Default")
      (node (ref "D0") (pin "3") (pinfunction "CK1_3") (pintype "passive"))
      (node (ref "D0") (pin "8") (pinfunction "CK2_8") (pintype "passive"))
      (node (ref "T1") (pin "3") (pinfunction "C_3") (pintype "passive"))
    )
    (net (code "148") (name "SIG_K1AA") (class "Default")
      (node (ref "D5") (pin "3") (pinfunction "CK1_3") (pintype "passive"))
      (node (ref "D5") (pin "8") (pinfunction "CK2_8") (pintype "passive"))
      (node (ref "T6") (pin "3") (pinfunction "C_3") (pintype "passive"))
    )
    (net (code "149") (name "SWITCH2_INH") (class "Default")
      (node (ref "IC5") (pin "15") (pinfunction "INH_15") (pintype "input"))
      (node (ref "U$1") (pin "10-CS\\MQSR") (pinfunction "10-CS/MQSR_10-CS\\MQSR") (pintype "bidirectional"))
    )
    (net (code "150") (name "SWITCH2_X") (class "Default")
      (node (ref "IC5") (pin "1") (pinfunction "X_1") (pintype "output"))
      (node (ref "U$1") (pin "18-A4/SDA0") (pinfunction "18-A4/SDA0_18-A4/SDA0") (pintype "bidirectional"))
    )
    (net (code "151") (name "SWITCH_INH") (class "Default")
      (node (ref "IC2") (pin "15") (pinfunction "INH_15") (pintype "input"))
      (node (ref "U$1") (pin "7-RX2/OUT1A") (pinfunction "7-RX2/OUT1A_7-RX2/OUT1A") (pintype "bidirectional"))
    )
    (net (code "152") (name "SWITCH_X") (class "Default")
      (node (ref "IC2") (pin "1") (pinfunction "X_1") (pintype "output"))
      (node (ref "U$1") (pin "15-A1/RX3/SPDIF_IN") (pinfunction "15-A1/RX3/SPDIF_IN_15-A1/RX3/SPDIF_IN") (pintype "bidirectional"))
    )
    (net (code "153") (name "unconnected-(IC1A-X10-Pad21)") (class "Default")
      (node (ref "IC1") (pin "21") (pinfunction "X10_21") (pintype "input"))
    )
    (net (code "154") (name "unconnected-(IC1A-X11-Pad20)") (class "Default")
      (node (ref "IC1") (pin "20") (pinfunction "X11_20") (pintype "input"))
    )
    (net (code "155") (name "unconnected-(IC1A-X12-Pad19)") (class "Default")
      (node (ref "IC1") (pin "19") (pinfunction "X12_19") (pintype "input"))
    )
    (net (code "156") (name "unconnected-(IC1A-X13-Pad18)") (class "Default")
      (node (ref "IC1") (pin "18") (pinfunction "X13_18") (pintype "input"))
    )
    (net (code "157") (name "unconnected-(IC1A-X14-Pad17)") (class "Default")
      (node (ref "IC1") (pin "17") (pinfunction "X14_17") (pintype "input"))
    )
    (net (code "158") (name "unconnected-(IC1A-X15-Pad16)") (class "Default")
      (node (ref "IC1") (pin "16") (pinfunction "X15_16") (pintype "input"))
    )
    (net (code "159") (name "unconnected-(IC2A-X10-Pad21)") (class "Default")
      (node (ref "IC2") (pin "21") (pinfunction "X10_21") (pintype "input"))
    )
    (net (code "160") (name "unconnected-(IC2A-X11-Pad20)") (class "Default")
      (node (ref "IC2") (pin "20") (pinfunction "X11_20") (pintype "input"))
    )
    (net (code "161") (name "unconnected-(IC2A-X12-Pad19)") (class "Default")
      (node (ref "IC2") (pin "19") (pinfunction "X12_19") (pintype "input"))
    )
    (net (code "162") (name "unconnected-(IC2A-X13-Pad18)") (class "Default")
      (node (ref "IC2") (pin "18") (pinfunction "X13_18") (pintype "input"))
    )
    (net (code "163") (name "unconnected-(IC2A-X14-Pad17)") (class "Default")
      (node (ref "IC2") (pin "17") (pinfunction "X14_17") (pintype "input"))
    )
    (net (code "164") (name "unconnected-(IC2A-X15-Pad16)") (class "Default")
      (node (ref "IC2") (pin "16") (pinfunction "X15_16") (pintype "input"))
    )
    (net (code "165") (name "unconnected-(IC3A-X10-Pad21)") (class "Default")
      (node (ref "IC3") (pin "21") (pinfunction "X10_21") (pintype "input"))
    )
    (net (code "166") (name "unconnected-(IC3A-X11-Pad20)") (class "Default")
      (node (ref "IC3") (pin "20") (pinfunction "X11_20") (pintype "input"))
    )
    (net (code "167") (name "unconnected-(IC3A-X12-Pad19)") (class "Default")
      (node (ref "IC3") (pin "19") (pinfunction "X12_19") (pintype "input"))
    )
    (net (code "168") (name "unconnected-(IC3A-X13-Pad18)") (class "Default")
      (node (ref "IC3") (pin "18") (pinfunction "X13_18") (pintype "input"))
    )
    (net (code "169") (name "unconnected-(IC3A-X14-Pad17)") (class "Default")
      (node (ref "IC3") (pin "17") (pinfunction "X14_17") (pintype "input"))
    )
    (net (code "170") (name "unconnected-(IC3A-X15-Pad16)") (class "Default")
      (node (ref "IC3") (pin "16") (pinfunction "X15_16") (pintype "input"))
    )
    (net (code "171") (name "unconnected-(IC4A-X10-Pad21)") (class "Default")
      (node (ref "IC4") (pin "21") (pinfunction "X10_21") (pintype "input"))
    )
    (net (code "172") (name "unconnected-(IC4A-X11-Pad20)") (class "Default")
      (node (ref "IC4") (pin "20") (pinfunction "X11_20") (pintype "input"))
    )
    (net (code "173") (name "unconnected-(IC4A-X12-Pad19)") (class "Default")
      (node (ref "IC4") (pin "19") (pinfunction "X12_19") (pintype "input"))
    )
    (net (code "174") (name "unconnected-(IC4A-X13-Pad18)") (class "Default")
      (node (ref "IC4") (pin "18") (pinfunction "X13_18") (pintype "input"))
    )
    (net (code "175") (name "unconnected-(IC4A-X14-Pad17)") (class "Default")
      (node (ref "IC4") (pin "17") (pinfunction "X14_17") (pintype "input"))
    )
    (net (code "176") (name "unconnected-(IC4A-X15-Pad16)") (class "Default")
      (node (ref "IC4") (pin "16") (pinfunction "X15_16") (pintype "input"))
    )
    (net (code "177") (name "unconnected-(IC5A-X10-Pad21)") (class "Default")
      (node (ref "IC5") (pin "21") (pinfunction "X10_21") (pintype "input"))
    )
    (net (code "178") (name "unconnected-(IC5A-X11-Pad20)") (class "Default")
      (node (ref "IC5") (pin "20") (pinfunction "X11_20") (pintype "input"))
    )
    (net (code "179") (name "unconnected-(IC5A-X12-Pad19)") (class "Default")
      (node (ref "IC5") (pin "19") (pinfunction "X12_19") (pintype "input"))
    )
    (net (code "180") (name "unconnected-(IC5A-X13-Pad18)") (class "Default")
      (node (ref "IC5") (pin "18") (pinfunction "X13_18") (pintype "input"))
    )
    (net (code "181") (name "unconnected-(IC5A-X14-Pad17)") (class "Default")
      (node (ref "IC5") (pin "17") (pinfunction "X14_17") (pintype "input"))
    )
    (net (code "182") (name "unconnected-(IC5A-X15-Pad16)") (class "Default")
      (node (ref "IC5") (pin "16") (pinfunction "X15_16") (pintype "input"))
    )
    (net (code "183") (name "unconnected-(MS0-S1-Pad2)") (class "Default")
      (node (ref "MS0") (pin "2") (pinfunction "S1_2") (pintype "passive"))
    )
    (net (code "184") (name "unconnected-(MS1-S1-Pad2)") (class "Default")
      (node (ref "MS1") (pin "2") (pinfunction "S1_2") (pintype "passive"))
    )
    (net (code "185") (name "unconnected-(MS2-S1-Pad2)") (class "Default")
      (node (ref "MS2") (pin "2") (pinfunction "S1_2") (pintype "passive"))
    )
    (net (code "186") (name "unconnected-(MS3-S1-Pad2)") (class "Default")
      (node (ref "MS3") (pin "2") (pinfunction "S1_2") (pintype "passive"))
    )
    (net (code "187") (name "unconnected-(MS4-S1-Pad2)") (class "Default")
      (node (ref "MS4") (pin "2") (pinfunction "S1_2") (pintype "passive"))
    )
    (net (code "188") (name "unconnected-(MS5-S1-Pad2)") (class "Default")
      (node (ref "MS5") (pin "2") (pinfunction "S1_2") (pintype "passive"))
    )
    (net (code "189") (name "unconnected-(MS6-S1-Pad2)") (class "Default")
      (node (ref "MS6") (pin "2") (pinfunction "S1_2") (pintype "passive"))
    )
    (net (code "190") (name "unconnected-(MS7-S1-Pad2)") (class "Default")
      (node (ref "MS7") (pin "2") (pinfunction "S1_2") (pintype "passive"))
    )
    (net (code "191") (name "unconnected-(MS8-S1-Pad2)") (class "Default")
      (node (ref "MS8") (pin "2") (pinfunction "S1_2") (pintype "passive"))
    )
    (net (code "192") (name "unconnected-(MS9-S1-Pad2)") (class "Default")
      (node (ref "MS9") (pin "2") (pinfunction "S1_2") (pintype "passive"))
    )
    (net (code "193") (name "unconnected-(SW0-S1-Pad2)") (class "Default")
      (node (ref "SW0") (pin "2") (pinfunction "S1_2") (pintype "passive"))
    )
    (net (code "194") (name "unconnected-(SW1-S1-Pad2)") (class "Default")
      (node (ref "SW1") (pin "2") (pinfunction "S1_2") (pintype "passive"))
    )
    (net (code "195") (name "unconnected-(SW2-S1-Pad2)") (class "Default")
      (node (ref "SW2") (pin "2") (pinfunction "S1_2") (pintype "passive"))
    )
    (net (code "196") (name "unconnected-(SW3-S1-Pad2)") (class "Default")
      (node (ref "SW3") (pin "2") (pinfunction "S1_2") (pintype "passive"))
    )
    (net (code "197") (name "unconnected-(SW4-S1-Pad2)") (class "Default")
      (node (ref "SW4") (pin "2") (pinfunction "S1_2") (pintype "passive"))
    )
    (net (code "198") (name "unconnected-(SW5-S1-Pad2)") (class "Default")
      (node (ref "SW5") (pin "2") (pinfunction "S1_2") (pintype "passive"))
    )
    (net (code "199") (name "unconnected-(SW6-S1-Pad2)") (class "Default")
      (node (ref "SW6") (pin "2") (pinfunction "S1_2") (pintype "passive"))
    )
    (net (code "200") (name "unconnected-(SW7-S1-Pad2)") (class "Default")
      (node (ref "SW7") (pin "2") (pinfunction "S1_2") (pintype "passive"))
    )
    (net (code "201") (name "unconnected-(SW8-S1-Pad2)") (class "Default")
      (node (ref "SW8") (pin "2") (pinfunction "S1_2") (pintype "passive"))
    )
    (net (code "202") (name "unconnected-(SW9-S1-Pad2)") (class "Default")
      (node (ref "SW9") (pin "2") (pinfunction "S1_2") (pintype "passive"))
    )
    (net (code "203") (name "unconnected-(U$1-5V-Pad+5V)") (class "Default")
      (node (ref "U$1") (pin "+5V") (pinfunction "5V_+5V") (pintype "bidirectional"))
    )
    (net (code "204") (name "unconnected-(U$1-Pad3V3-1)") (class "Default")
      (node (ref "U$1") (pin "3V3-1") (pinfunction "3V3-1_3V3-1") (pintype "bidirectional"))
    )
    (net (code "205") (name "unconnected-(U$1-Pad3V3-2)") (class "Default")
      (node (ref "U$1") (pin "3V3-2") (pinfunction "3V3-2_3V3-2") (pintype "bidirectional"))
    )
    (net (code "206") (name "unconnected-(U$1-PadD+)") (class "Default")
      (node (ref "U$1") (pin "D+") (pinfunction "D+_D+") (pintype "bidirectional"))
    )
    (net (code "207") (name "unconnected-(U$1-PadD-)") (class "Default")
      (node (ref "U$1") (pin "D-") (pinfunction "D-_D-") (pintype "bidirectional"))
    )
    (net (code "208") (name "unconnected-(U$1-PadDM)") (class "Default")
      (node (ref "U$1") (pin "DM") (pinfunction "DM_DM") (pintype "bidirectional"))
    )
    (net (code "209") (name "unconnected-(U$1-PadDP)") (class "Default")
      (node (ref "U$1") (pin "DP") (pinfunction "DP_DP") (pintype "bidirectional"))
    )
    (net (code "210") (name "unconnected-(U$1-PadG)") (class "Default")
      (node (ref "U$1") (pin "G") (pinfunction "G_G") (pintype "bidirectional"))
    )
    (net (code "211") (name "unconnected-(U$1-PadGND2)") (class "Default")
      (node (ref "U$1") (pin "GND2") (pinfunction "GND2_GND2") (pintype "bidirectional"))
    )
    (net (code "212") (name "unconnected-(U$1-PadGND3)") (class "Default")
      (node (ref "U$1") (pin "GND3") (pinfunction "GND3_GND3") (pintype "bidirectional"))
    )
    (net (code "213") (name "unconnected-(U$1-PadGND4)") (class "Default")
      (node (ref "U$1") (pin "GND4") (pinfunction "GND4_GND4") (pintype "bidirectional"))
    )
    (net (code "214") (name "unconnected-(U$1-PadGND5)") (class "Default")
      (node (ref "U$1") (pin "GND5") (pinfunction "GND5_GND5") (pintype "bidirectional"))
    )
    (net (code "215") (name "unconnected-(U$1-PadGND6)") (class "Default")
      (node (ref "U$1") (pin "GND6") (pinfunction "GND6_GND6") (pintype "bidirectional"))
    )
    (net (code "216") (name "unconnected-(U$1-PadLED)") (class "Default")
      (node (ref "U$1") (pin "LED") (pinfunction "LED_LED") (pintype "bidirectional"))
    )
    (net (code "217") (name "unconnected-(U$1-PadON{slash}OFF)") (class "Default")
      (node (ref "U$1") (pin "ON/OFF") (pinfunction "ON/OFF_ON/OFF") (pintype "bidirectional"))
    )
    (net (code "218") (name "unconnected-(U$1-PadPROGRAM)") (class "Default")
      (node (ref "U$1") (pin "PROGRAM") (pinfunction "PROGRAM_PROGRAM") (pintype "bidirectional"))
    )
    (net (code "219") (name "unconnected-(U$1-PadR+)") (class "Default")
      (node (ref "U$1") (pin "R+") (pinfunction "R+_R+") (pintype "bidirectional"))
    )
    (net (code "220") (name "unconnected-(U$1-PadR-)") (class "Default")
      (node (ref "U$1") (pin "R-") (pinfunction "R-_R-") (pintype "bidirectional"))
    )
    (net (code "221") (name "unconnected-(U$1-PadT+)") (class "Default")
      (node (ref "U$1") (pin "T+") (pinfunction "T+_T+") (pintype "bidirectional"))
    )
    (net (code "222") (name "unconnected-(U$1-PadT-)") (class "Default")
      (node (ref "U$1") (pin "T-") (pinfunction "T-_T-") (pintype "bidirectional"))
    )
    (net (code "223") (name "unconnected-(U$1-PadVBAT)") (class "Default")
      (node (ref "U$1") (pin "VBAT") (pinfunction "VBAT_VBAT") (pintype "bidirectional"))
    )
    (net (code "224") (name "unconnected-(U$1-PadVIN)") (class "Default")
      (node (ref "U$1") (pin "VIN") (pinfunction "VIN_VIN") (pintype "bidirectional"))
    )
    (net (code "225") (name "unconnected-(U$1-PadVUSB)") (class "Default")
      (node (ref "U$1") (pin "VUSB") (pinfunction "VUSB_VUSB") (pintype "bidirectional"))
    )
  )
)
